# Tango_V1_0.net
KiCad netlist of a schematic drawn in Altium Designer
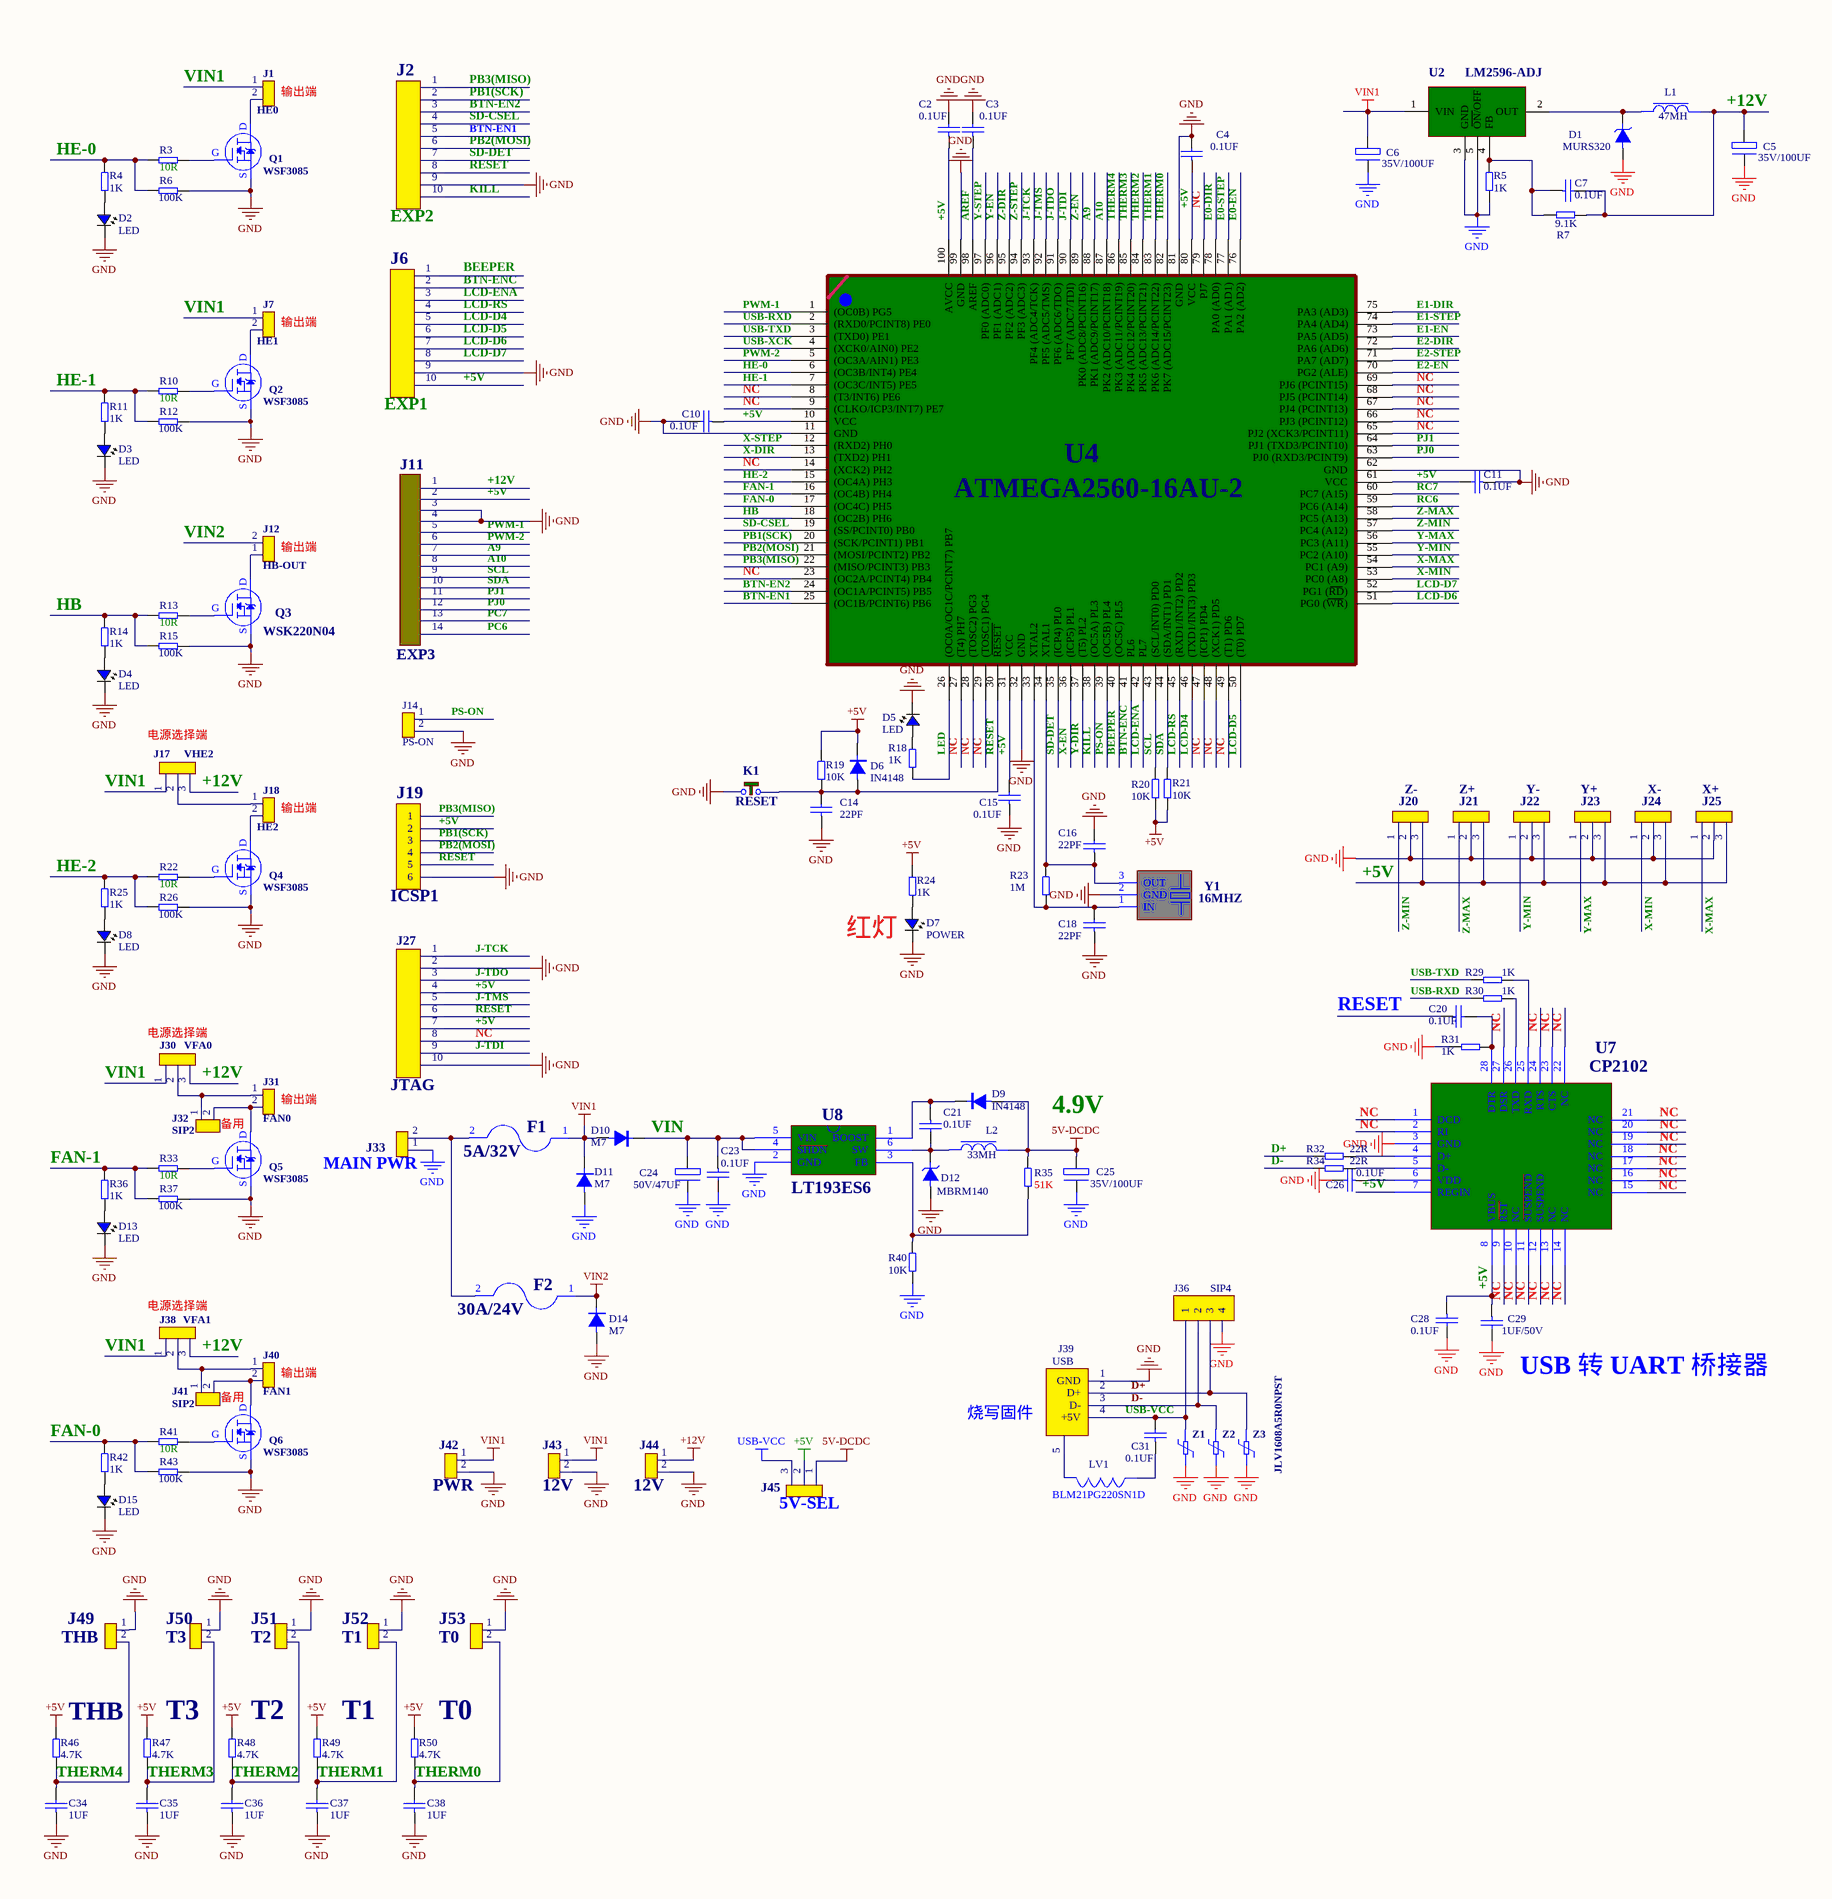
[diagram p0: Tango V1.0.SchDoc, left]
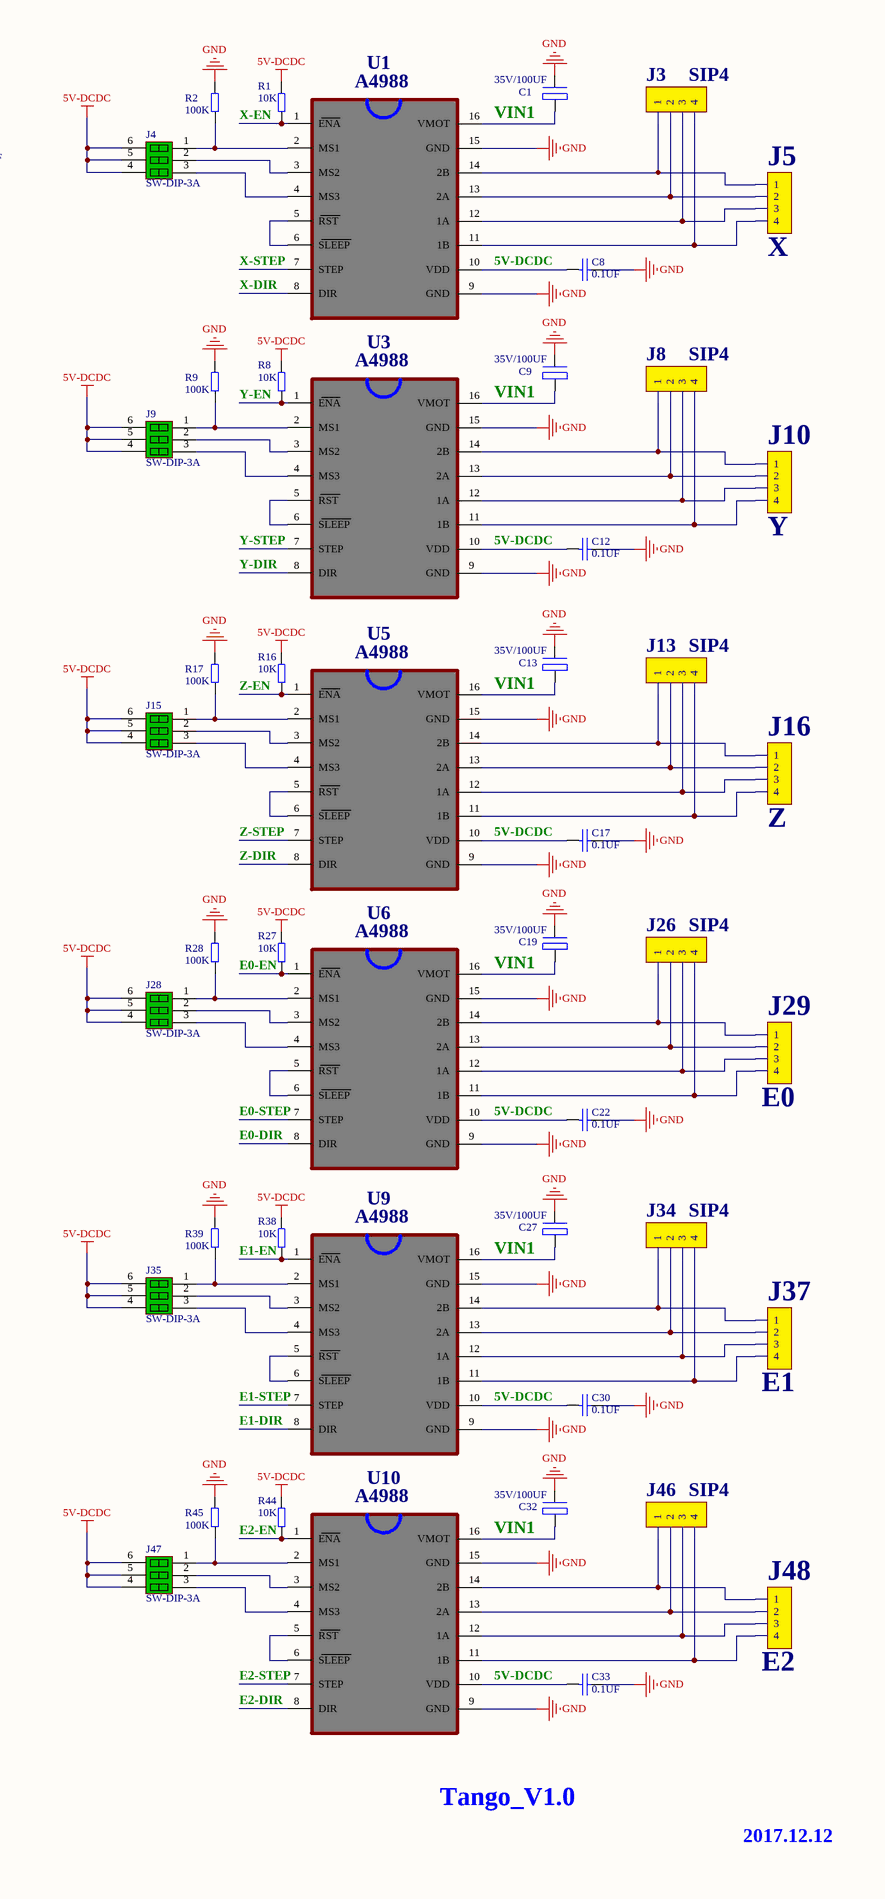
[diagram p1: Tango V1.0.SchDoc, right]

(export (version "E")
  (design (tool "Eeschema 10.0.6"))
  (components
    (comp (ref "C1") (value "35V/100UF") (footprint "35V/100UF-2") (libsource (lib "liroqi") (part "C")))
    (comp (ref "C2") (value "0.1UF") (footprint "0603N") (libsource (lib "liroqi") (part "CAP")))
    (comp (ref "C3") (value "0.1UF") (footprint "0603N") (libsource (lib "liroqi") (part "CAP")))
    (comp (ref "C4") (value "0.1UF") (footprint "0603N") (libsource (lib "liroqi") (part "CAP")))
    (comp (ref "C5") (value "35V/100UF") (footprint "35V/100UF-2") (libsource (lib "liroqi") (part "C")))
    (comp (ref "C6") (value "35V/100UF") (footprint "35V/100UF-2") (libsource (lib "liroqi") (part "C")))
    (comp (ref "C7") (value "0.1UF") (footprint "0603N") (libsource (lib "liroqi") (part "CAP")))
    (comp (ref "C8") (value "0.1UF") (footprint "0603N") (libsource (lib "liroqi") (part "CAP")))
    (comp (ref "C9") (value "35V/100UF") (footprint "35V/100UF-2") (libsource (lib "liroqi") (part "C")))
    (comp (ref "C10") (value "0.1UF") (footprint "0603N") (libsource (lib "liroqi") (part "CAP")))
    (comp (ref "C11") (value "0.1UF") (footprint "0603N") (libsource (lib "liroqi") (part "CAP")))
    (comp (ref "C12") (value "0.1UF") (footprint "0603N") (libsource (lib "liroqi") (part "CAP")))
    (comp (ref "C13") (value "35V/100UF") (footprint "35V/100UF-2") (libsource (lib "liroqi") (part "C")))
    (comp (ref "C14") (value "22PF") (footprint "0603N") (libsource (lib "liroqi") (part "CAP")))
    (comp (ref "C15") (value "0.1UF") (footprint "0603N") (libsource (lib "liroqi") (part "CAP")))
    (comp (ref "C16") (value "22PF") (footprint "0603N") (libsource (lib "liroqi") (part "CAP")))
    (comp (ref "C17") (value "0.1UF") (footprint "0603N") (libsource (lib "liroqi") (part "CAP")))
    (comp (ref "C18") (value "22PF") (footprint "0603N") (libsource (lib "liroqi") (part "CAP")))
    (comp (ref "C19") (value "35V/100UF") (footprint "35V/100UF-2") (libsource (lib "liroqi") (part "C")))
    (comp (ref "C20") (value "0.1UF") (footprint "0603N") (libsource (lib "liroqi") (part "CAP")))
    (comp (ref "C21") (value "0.1UF") (footprint "0603N") (libsource (lib "liroqi") (part "CAP")))
    (comp (ref "C22") (value "0.1UF") (footprint "0603N") (libsource (lib "liroqi") (part "CAP")))
    (comp (ref "C23") (value "0.1UF") (footprint "0603N") (libsource (lib "liroqi") (part "CAP")))
    (comp (ref "C24") (value "50V/47UF") (footprint "35V/100UF-2") (libsource (lib "liroqi") (part "C")))
    (comp (ref "C25") (value "35V/100UF") (footprint "35V/100UF-2") (libsource (lib "liroqi") (part "C")))
    (comp (ref "C26") (value "0.1UF") (footprint "0603N") (libsource (lib "liroqi") (part "CAP")))
    (comp (ref "C27") (value "35V/100UF") (footprint "35V/100UF-2") (libsource (lib "liroqi") (part "C")))
    (comp (ref "C28") (value "0.1UF") (footprint "0603N") (libsource (lib "liroqi") (part "CAP")))
    (comp (ref "C29") (value "1UF/50V") (footprint "0603N") (libsource (lib "liroqi") (part "CAP")))
    (comp (ref "C30") (value "0.1UF") (footprint "0603N") (libsource (lib "liroqi") (part "CAP")))
    (comp (ref "C31") (value "0.1UF") (footprint "0603N") (libsource (lib "liroqi") (part "CAP")))
    (comp (ref "C32") (value "35V/100UF") (footprint "35V/100UF-2") (libsource (lib "liroqi") (part "C")))
    (comp (ref "C33") (value "0.1UF") (footprint "0603N") (libsource (lib "liroqi") (part "CAP")))
    (comp (ref "C34") (value "1UF") (footprint "0805N") (libsource (lib "liroqi") (part "CAP")))
    (comp (ref "C35") (value "1UF") (footprint "0805N") (libsource (lib "liroqi") (part "CAP")))
    (comp (ref "C36") (value "1UF") (footprint "0805N") (libsource (lib "liroqi") (part "CAP")))
    (comp (ref "C37") (value "1UF") (footprint "0805N") (libsource (lib "liroqi") (part "CAP")))
    (comp (ref "C38") (value "1UF") (footprint "0805N") (libsource (lib "liroqi") (part "CAP")))
    (comp (ref "D1") (value "MURS320") (footprint "DO-214AB") (libsource (lib "liroqi") (part "ZENEVR")))
    (comp (ref "D2") (value "LED") (footprint "LED-0603") (libsource (lib "liroqi") (part "LED")))
    (comp (ref "D3") (value "LED") (footprint "LED-0603") (libsource (lib "liroqi") (part "LED")))
    (comp (ref "D4") (value "LED") (footprint "LED-0603") (libsource (lib "liroqi") (part "LED")))
    (comp (ref "D5") (value "LED") (footprint "LED-0603") (libsource (lib "liroqi") (part "LED")))
    (comp (ref "D6") (value "IN4148") (footprint "1206-DIDEO") (libsource (lib "liroqi") (part "DIODE")))
    (comp (ref "D7") (value "POWER") (footprint "LED-0603") (libsource (lib "liroqi") (part "LED")))
    (comp (ref "D8") (value "LED") (footprint "LED-0603") (libsource (lib "liroqi") (part "LED")))
    (comp (ref "D9") (value "IN4148") (footprint "1206-DIDEO") (libsource (lib "liroqi") (part "DIODE")))
    (comp (ref "D10") (value "M7") (footprint "DO-214AC") (libsource (lib "liroqi") (part "DIODE")))
    (comp (ref "D11") (value "M7") (footprint "DO-214AC") (libsource (lib "liroqi") (part "DIODE")))
    (comp (ref "D12") (value "MBRM140") (footprint "MBRM140") (libsource (lib "liroqi") (part "ZENEVR")))
    (comp (ref "D13") (value "LED") (footprint "LED-0603") (libsource (lib "liroqi") (part "LED")))
    (comp (ref "D14") (value "M7") (footprint "DO-214AC") (libsource (lib "liroqi") (part "DIODE")))
    (comp (ref "D15") (value "LED") (footprint "LED-0603") (libsource (lib "liroqi") (part "LED")))
    (comp (ref "F1") (value "5A/32V") (footprint "1206") (libsource (lib "liroqi") (part "FUSE")))
    (comp (ref "F2") (value "30A/24V") (footprint "1206") (libsource (lib "liroqi") (part "FUSE")))
    (comp (ref "J1") (value "HE0") (footprint "5.08-2-B") (libsource (lib "") (part "SIP2_1")))
    (comp (ref "J2") (value "EXP2") (footprint "IDC10-2.54") (libsource (lib "liroqi") (part "SIP10")))
    (comp (ref "J3") (value "SIP4") (footprint "SIP4") (libsource (lib "") (part "SIP4_1")))
    (comp (ref "J4")
      (value "SW-DIP-3A")
      (footprint "Header 3X2-B")
      (libsource (lib "liroqi") (part "SW-DIP-3A"))
    )
    (comp (ref "J5") (value "X") (footprint "2.54-4P-2") (libsource (lib "liroqi") (part "SIP4")))
    (comp (ref "J6") (value "EXP1") (footprint "IDC10-2.54") (libsource (lib "liroqi") (part "SIP10")))
    (comp (ref "J7") (value "HE1") (footprint "5.08-2-B") (libsource (lib "") (part "SIP2_1")))
    (comp (ref "J8") (value "SIP4") (footprint "SIP4") (libsource (lib "") (part "SIP4_1")))
    (comp (ref "J9")
      (value "SW-DIP-3A")
      (footprint "Header 3X2-B")
      (libsource (lib "liroqi") (part "SW-DIP-3A"))
    )
    (comp (ref "J10") (value "Y") (footprint "2.54-4P-2") (libsource (lib "liroqi") (part "SIP4")))
    (comp (ref "J11") (value "EXP3") (footprint "Header 7X2") (libsource (lib "liroqi") (part "SIP14")))
    (comp (ref "J12") (value "HB-OUT") (footprint "5.08-2") (libsource (lib "") (part "SIP2_3")))
    (comp (ref "J13") (value "SIP4") (footprint "SIP4") (libsource (lib "") (part "SIP4_1")))
    (comp (ref "J14") (value "PS-ON") (footprint "SIP2") (libsource (lib "") (part "SIP2_2")))
    (comp (ref "J15")
      (value "SW-DIP-3A")
      (footprint "Header 3X2-B")
      (libsource (lib "liroqi") (part "SW-DIP-3A"))
    )
    (comp (ref "J16") (value "Z") (footprint "2.54-4P-2") (libsource (lib "liroqi") (part "SIP4")))
    (comp (ref "J17") (value "VHE2") (footprint "SIP3") (libsource (lib "liroqi") (part "SIP3")))
    (comp (ref "J18") (value "HE2") (footprint "5.08-2-B") (libsource (lib "") (part "SIP2_1")))
    (comp (ref "J19") (value "ICSP1") (footprint "Header 3X2") (libsource (lib "liroqi") (part "SIP6")))
    (comp (ref "J20") (value "Z-") (footprint "2.54-3P-2") (libsource (lib "liroqi") (part "SIP3")))
    (comp (ref "J21") (value "Z+") (footprint "2.54-3P-2") (libsource (lib "liroqi") (part "SIP3")))
    (comp (ref "J22") (value "Y-") (footprint "2.54-3P-2") (libsource (lib "liroqi") (part "SIP3")))
    (comp (ref "J23") (value "Y+") (footprint "2.54-3P-2") (libsource (lib "liroqi") (part "SIP3")))
    (comp (ref "J24") (value "X-") (footprint "2.54-3P-2") (libsource (lib "liroqi") (part "SIP3")))
    (comp (ref "J25") (value "X+") (footprint "2.54-3P-2") (libsource (lib "liroqi") (part "SIP3")))
    (comp (ref "J26") (value "SIP4") (footprint "SIP4") (libsource (lib "") (part "SIP4_1")))
    (comp (ref "J27") (value "JTAG") (footprint "Header 5X2") (libsource (lib "liroqi") (part "SIP10")))
    (comp (ref "J28")
      (value "SW-DIP-3A")
      (footprint "Header 3X2-B")
      (libsource (lib "liroqi") (part "SW-DIP-3A"))
    )
    (comp (ref "J29") (value "E0") (footprint "2.54-4P-2") (libsource (lib "liroqi") (part "SIP4")))
    (comp (ref "J30") (value "VFA0") (footprint "SIP3") (libsource (lib "liroqi") (part "SIP3")))
    (comp (ref "J31") (value "FAN0") (footprint "5.08-2-B") (libsource (lib "") (part "SIP2_1")))
    (comp (ref "J32") (value "SIP2") (footprint "SIP2") (libsource (lib "liroqi") (part "SIP2")))
    (comp (ref "J33") (value "MAIN PWR") (footprint "5.08-2") (libsource (lib "liroqi") (part "SIP2")))
    (comp (ref "J34") (value "SIP4") (footprint "SIP4") (libsource (lib "") (part "SIP4_1")))
    (comp (ref "J35")
      (value "SW-DIP-3A")
      (footprint "Header 3X2-B")
      (libsource (lib "liroqi") (part "SW-DIP-3A"))
    )
    (comp (ref "J36") (value "SIP4") (footprint "SIP4") (libsource (lib "") (part "SIP4_1")))
    (comp (ref "J37") (value "E1") (footprint "2.54-4P-2") (libsource (lib "liroqi") (part "SIP4")))
    (comp (ref "J38") (value "VFA1") (footprint "SIP3") (libsource (lib "liroqi") (part "SIP3")))
    (comp (ref "J39") (value "USB") (footprint "USB-B-3") (libsource (lib "liroqi") (part "SIP5-USB")))
    (comp (ref "J40") (value "FAN1") (footprint "5.08-2-B") (libsource (lib "") (part "SIP2_1")))
    (comp (ref "J41") (value "SIP2") (footprint "SIP2") (libsource (lib "liroqi") (part "SIP2")))
    (comp (ref "J42") (value "PWR") (footprint "SIP2") (libsource (lib "") (part "SIP2_2")))
    (comp (ref "J43") (value "12V") (footprint "2.54-2P-2") (libsource (lib "") (part "SIP2_2")))
    (comp (ref "J44") (value "12V") (footprint "2.54-2P-2") (libsource (lib "") (part "SIP2_2")))
    (comp (ref "J45") (value "5V-SEL") (footprint "SIP3") (libsource (lib "") (part "SIP3_1")))
    (comp (ref "J46") (value "SIP4") (footprint "SIP4") (libsource (lib "") (part "SIP4_1")))
    (comp (ref "J47")
      (value "SW-DIP-3A")
      (footprint "Header 3X2-B")
      (libsource (lib "liroqi") (part "SW-DIP-3A"))
    )
    (comp (ref "J48") (value "E2") (footprint "2.54-4P-2") (libsource (lib "liroqi") (part "SIP4")))
    (comp (ref "J49") (value "THB") (footprint "2.54-2P-2") (libsource (lib "") (part "SIP2_2")))
    (comp (ref "J50") (value "T3") (footprint "2.54-2P-2") (libsource (lib "") (part "SIP2_2")))
    (comp (ref "J51") (value "T2") (footprint "2.54-2P-2") (libsource (lib "") (part "SIP2_2")))
    (comp (ref "J52") (value "T1") (footprint "2.54-2P-2") (libsource (lib "") (part "SIP2_2")))
    (comp (ref "J53") (value "T0") (footprint "2.54-2P-2") (libsource (lib "") (part "SIP2_2")))
    (comp (ref "K1") (value "RESET") (footprint "K-VX") (libsource (lib "liroqi") (part "K3")))
    (comp (ref "L1") (value "47MH") (footprint "15MH") (libsource (lib "liroqi") (part "L1")))
    (comp (ref "L2") (value "33MH") (footprint "7.5*7.5") (libsource (lib "liroqi") (part "L1")))
    (comp (ref "LV1") (value "BLM21PG220SN1D") (footprint "0805N") (libsource (lib "liroqi") (part "L")))
    (comp (ref "Q1") (value "WSF3085") (footprint "TO-252-B") (libsource (lib "liroqi") (part "VS3060AD")))
    (comp (ref "Q2") (value "WSF3085") (footprint "TO-252-B") (libsource (lib "liroqi") (part "VS3060AD")))
    (comp (ref "Q3") (value "WSK220N04") (footprint "TO-263-B") (libsource (lib "liroqi") (part "NMOS")))
    (comp (ref "Q4") (value "WSF3085") (footprint "TO-252-B") (libsource (lib "liroqi") (part "VS3060AD")))
    (comp (ref "Q5") (value "WSF3085") (footprint "TO-252-B") (libsource (lib "liroqi") (part "VS3060AD")))
    (comp (ref "Q6") (value "WSF3085") (footprint "TO-252-B") (libsource (lib "liroqi") (part "VS3060AD")))
    (comp (ref "R1") (value "10K") (footprint "0603N") (libsource (lib "liroqi") (part "RES")))
    (comp (ref "R2") (value "100K") (footprint "0603N") (libsource (lib "liroqi") (part "RES")))
    (comp (ref "R3") (value "10R") (footprint "0603N") (libsource (lib "liroqi") (part "RES")))
    (comp (ref "R4") (value "1K") (footprint "0603N") (libsource (lib "liroqi") (part "RES")))
    (comp (ref "R5") (value "1K") (footprint "0603N") (libsource (lib "liroqi") (part "RES")))
    (comp (ref "R6") (value "100K") (footprint "0603N") (libsource (lib "liroqi") (part "RES")))
    (comp (ref "R7") (value "9.1K") (footprint "0603N") (libsource (lib "liroqi") (part "RES")))
    (comp (ref "R8") (value "10K") (footprint "0603N") (libsource (lib "liroqi") (part "RES")))
    (comp (ref "R9") (value "100K") (footprint "0603N") (libsource (lib "liroqi") (part "RES")))
    (comp (ref "R10") (value "10R") (footprint "0603N") (libsource (lib "liroqi") (part "RES")))
    (comp (ref "R11") (value "1K") (footprint "0603N") (libsource (lib "liroqi") (part "RES")))
    (comp (ref "R12") (value "100K") (footprint "0603N") (libsource (lib "liroqi") (part "RES")))
    (comp (ref "R13") (value "10R") (footprint "0603N") (libsource (lib "liroqi") (part "RES")))
    (comp (ref "R14") (value "1K") (footprint "0603N") (libsource (lib "liroqi") (part "RES")))
    (comp (ref "R15") (value "100K") (footprint "0603N") (libsource (lib "liroqi") (part "RES")))
    (comp (ref "R16") (value "10K") (footprint "0603N") (libsource (lib "liroqi") (part "RES")))
    (comp (ref "R17") (value "100K") (footprint "0603N") (libsource (lib "liroqi") (part "RES")))
    (comp (ref "R18") (value "1K") (footprint "0603N") (libsource (lib "liroqi") (part "RES")))
    (comp (ref "R19") (value "10K") (footprint "0603N") (libsource (lib "liroqi") (part "RES")))
    (comp (ref "R20") (value "10K") (footprint "0603N") (libsource (lib "liroqi") (part "RES")))
    (comp (ref "R21") (value "10K") (footprint "0603N") (libsource (lib "liroqi") (part "RES")))
    (comp (ref "R22") (value "10R") (footprint "0603N") (libsource (lib "liroqi") (part "RES")))
    (comp (ref "R23") (value "1M") (footprint "0603N") (libsource (lib "liroqi") (part "RES")))
    (comp (ref "R24") (value "1K") (footprint "0603N") (libsource (lib "liroqi") (part "RES")))
    (comp (ref "R25") (value "1K") (footprint "0603N") (libsource (lib "liroqi") (part "RES")))
    (comp (ref "R26") (value "100K") (footprint "0603N") (libsource (lib "liroqi") (part "RES")))
    (comp (ref "R27") (value "10K") (footprint "0603N") (libsource (lib "liroqi") (part "RES")))
    (comp (ref "R28") (value "100K") (footprint "0603N") (libsource (lib "liroqi") (part "RES")))
    (comp (ref "R29") (value "1K") (footprint "0603N") (libsource (lib "liroqi") (part "RES")))
    (comp (ref "R30") (value "1K") (footprint "0603N") (libsource (lib "liroqi") (part "RES")))
    (comp (ref "R31") (value "1K") (footprint "0603N") (libsource (lib "liroqi") (part "RES")))
    (comp (ref "R32") (value "22R") (footprint "0603N") (libsource (lib "liroqi") (part "RES")))
    (comp (ref "R33") (value "10R") (footprint "0603N") (libsource (lib "liroqi") (part "RES")))
    (comp (ref "R34") (value "22R") (footprint "0603N") (libsource (lib "liroqi") (part "RES")))
    (comp (ref "R35") (value "51K") (footprint "0603N") (libsource (lib "liroqi") (part "RES")))
    (comp (ref "R36") (value "1K") (footprint "0603N") (libsource (lib "liroqi") (part "RES")))
    (comp (ref "R37") (value "100K") (footprint "0603N") (libsource (lib "liroqi") (part "RES")))
    (comp (ref "R38") (value "10K") (footprint "0603N") (libsource (lib "liroqi") (part "RES")))
    (comp (ref "R39") (value "100K") (footprint "0603N") (libsource (lib "liroqi") (part "RES")))
    (comp (ref "R40") (value "10K") (footprint "0603N") (libsource (lib "liroqi") (part "RES")))
    (comp (ref "R41") (value "10R") (footprint "0603N") (libsource (lib "liroqi") (part "RES")))
    (comp (ref "R42") (value "1K") (footprint "0603N") (libsource (lib "liroqi") (part "RES")))
    (comp (ref "R43") (value "100K") (footprint "0603N") (libsource (lib "liroqi") (part "RES")))
    (comp (ref "R44") (value "10K") (footprint "0603N") (libsource (lib "liroqi") (part "RES")))
    (comp (ref "R45") (value "100K") (footprint "0603N") (libsource (lib "liroqi") (part "RES")))
    (comp (ref "R46") (value "4.7K") (footprint "0603N") (libsource (lib "liroqi") (part "RES")))
    (comp (ref "R47") (value "4.7K") (footprint "0603N") (libsource (lib "liroqi") (part "RES")))
    (comp (ref "R48") (value "4.7K") (footprint "0603N") (libsource (lib "liroqi") (part "RES")))
    (comp (ref "R49") (value "4.7K") (footprint "0603N") (libsource (lib "liroqi") (part "RES")))
    (comp (ref "R50") (value "4.7K") (footprint "0603N") (libsource (lib "liroqi") (part "RES")))
    (comp (ref "U1") (value "A4988") (footprint "A4988") (libsource (lib "liroqi") (part "A4988")))
    (comp (ref "U2") (value "LM2596-ADJ") (footprint "TO-263(S)") (libsource (lib "liroqi") (part "LM2596")))
    (comp (ref "U3") (value "A4988") (footprint "A4988") (libsource (lib "liroqi") (part "A4988")))
    (comp (ref "U4")
      (value "ATMEGA2560-16AU-2")
      (footprint "TQFP-100-B")
      (libsource (lib "liroqi") (part "ATMEGA2560-16AU-2"))
    )
    (comp (ref "U5") (value "A4988") (footprint "A4988") (libsource (lib "liroqi") (part "A4988")))
    (comp (ref "U6") (value "A4988") (footprint "A4988") (libsource (lib "liroqi") (part "A4988")))
    (comp (ref "U7") (value "CP2102") (footprint "QFN-28") (libsource (lib "liroqi") (part "CP2102")))
    (comp (ref "U8") (value "LT193ES6") (footprint "SOT23-6") (libsource (lib "liroqi") (part "LT1933ES6")))
    (comp (ref "U9") (value "A4988") (footprint "A4988") (libsource (lib "liroqi") (part "A4988")))
    (comp (ref "U10") (value "A4988") (footprint "A4988") (libsource (lib "liroqi") (part "A4988")))
    (comp (ref "Y1") (value "16MHZ") (footprint "SMD-3") (libsource (lib "liroqi") (part "SMD-3")))
    (comp (ref "Z1") (value "JLV1608A5R0NPST") (footprint "0603N") (libsource (lib "liroqi") (part "RV?")))
    (comp (ref "Z2") (value "JLV1608A5R0NPST") (footprint "0603N") (libsource (lib "liroqi") (part "RV?")))
    (comp (ref "Z3") (value "JLV1608A5R0NPST") (footprint "0603N") (libsource (lib "liroqi") (part "RV?")))
  )
  (nets
    (net (code "1") (name "+5V") (class "Default")
      (node (ref "C10") (pin "1") (pinfunction "1_1") (pintype "passive"))
      (node (ref "C11") (pin "2") (pinfunction "2_2") (pintype "passive"))
      (node (ref "C15") (pin "2") (pinfunction "2_2") (pintype "passive"))
      (node (ref "C2") (pin "1") (pinfunction "1_1") (pintype "passive"))
      (node (ref "C28") (pin "1") (pinfunction "1_1") (pintype "passive"))
      (node (ref "C29") (pin "1") (pinfunction "1_1") (pintype "passive"))
      (node (ref "C4") (pin "1") (pinfunction "1_1") (pintype "passive"))
      (node (ref "D6") (pin "2") (pinfunction "K_2") (pintype "passive"))
      (node (ref "J11") (pin "2") (pinfunction "2_2") (pintype "passive"))
      (node (ref "J19") (pin "2") (pinfunction "2_2") (pintype "passive"))
      (node (ref "J20") (pin "3") (pinfunction "3_3") (pintype "passive"))
      (node (ref "J21") (pin "3") (pinfunction "3_3") (pintype "passive"))
      (node (ref "J22") (pin "3") (pinfunction "3_3") (pintype "passive"))
      (node (ref "J23") (pin "3") (pinfunction "3_3") (pintype "passive"))
      (node (ref "J24") (pin "3") (pinfunction "3_3") (pintype "passive"))
      (node (ref "J25") (pin "3") (pinfunction "3_3") (pintype "passive"))
      (node (ref "J27") (pin "4") (pinfunction "4_4") (pintype "passive"))
      (node (ref "J27") (pin "7") (pinfunction "7_7") (pintype "passive"))
      (node (ref "J45") (pin "2") (pinfunction "2_2") (pintype "passive"))
      (node (ref "J6") (pin "10") (pinfunction "10_10") (pintype "passive"))
      (node (ref "R19") (pin "1") (pinfunction "1_1") (pintype "passive"))
      (node (ref "R20") (pin "2") (pinfunction "2_2") (pintype "passive"))
      (node (ref "R21") (pin "2") (pinfunction "2_2") (pintype "passive"))
      (node (ref "R24") (pin "2") (pinfunction "2_2") (pintype "passive"))
      (node (ref "R46") (pin "1") (pinfunction "1_1") (pintype "passive"))
      (node (ref "R47") (pin "1") (pinfunction "1_1") (pintype "passive"))
      (node (ref "R48") (pin "1") (pinfunction "1_1") (pintype "passive"))
      (node (ref "R49") (pin "1") (pinfunction "1_1") (pintype "passive"))
      (node (ref "R50") (pin "1") (pinfunction "1_1") (pintype "passive"))
      (node (ref "U4") (pin "10") (pinfunction "VCC_10") (pintype "passive"))
      (node (ref "U4") (pin "100") (pinfunction "AVCC_100") (pintype "passive"))
      (node (ref "U4") (pin "31") (pinfunction "VCC_31") (pintype "passive"))
      (node (ref "U4") (pin "61") (pinfunction "VCC_61") (pintype "passive"))
      (node (ref "U4") (pin "80") (pinfunction "VCC_80") (pintype "passive"))
      (node (ref "U7") (pin "7") (pinfunction "REGIN_7") (pintype "passive"))
      (node (ref "U7") (pin "8") (pinfunction "VBUS_8") (pintype "passive"))
    )
    (net (code "2") (name "+12V") (class "Default")
      (node (ref "C5") (pin "1") (pinfunction "+_1") (pintype "passive"))
      (node (ref "C7") (pin "2") (pinfunction "2_2") (pintype "passive"))
      (node (ref "J11") (pin "1") (pinfunction "1_1") (pintype "passive"))
      (node (ref "J17") (pin "3") (pinfunction "3_3") (pintype "passive"))
      (node (ref "J30") (pin "3") (pinfunction "3_3") (pintype "passive"))
      (node (ref "J38") (pin "3") (pinfunction "3_3") (pintype "passive"))
      (node (ref "J44") (pin "1") (pinfunction "1_1") (pintype "passive"))
      (node (ref "L1") (pin "2") (pinfunction "2_2") (pintype "passive"))
      (node (ref "R7") (pin "2") (pinfunction "2_2") (pintype "passive"))
    )
    (net (code "3") (name "/A9") (class "Default")
      (node (ref "J11") (pin "7") (pinfunction "7_7") (pintype "passive"))
      (node (ref "U4") (pin "88") (pinfunction "PK1_(ADC9/PCINT17)_88") (pintype "passive"))
    )
    (net (code "4") (name "/A10") (class "Default")
      (node (ref "J11") (pin "8") (pinfunction "8_8") (pintype "passive"))
      (node (ref "U4") (pin "87") (pinfunction "PK2_(ADC10/PCINT18)_87") (pintype "passive"))
    )
    (net (code "5") (name "/AREF") (class "Default")
      (node (ref "C3") (pin "1") (pinfunction "1_1") (pintype "passive"))
      (node (ref "U4") (pin "98") (pinfunction "AREF_98") (pintype "passive"))
    )
    (net (code "6") (name "/BEEPER") (class "Default")
      (node (ref "J6") (pin "1") (pinfunction "1_1") (pintype "passive"))
      (node (ref "U4") (pin "40") (pinfunction "(OC5C)_PL5_40") (pintype "passive"))
    )
    (net (code "7") (name "/BTN-EN1") (class "Default")
      (node (ref "J2") (pin "5") (pinfunction "5_5") (pintype "passive"))
      (node (ref "U4") (pin "25") (pinfunction "(OC1B/PCINT6)_PB6_25") (pintype "passive"))
    )
    (net (code "8") (name "/BTN-EN2") (class "Default")
      (node (ref "J2") (pin "3") (pinfunction "3_3") (pintype "passive"))
      (node (ref "U4") (pin "24") (pinfunction "(OC1A/PCINT5)_PB5_24") (pintype "passive"))
    )
    (net (code "9") (name "/BTN-ENC") (class "Default")
      (node (ref "J6") (pin "2") (pinfunction "2_2") (pintype "passive"))
      (node (ref "U4") (pin "41") (pinfunction "PL6_41") (pintype "passive"))
    )
    (net (code "10") (name "/D+") (class "Default")
      (node (ref "J36") (pin "3") (pinfunction "3_3") (pintype "passive"))
      (node (ref "J39") (pin "2") (pinfunction "D+_2") (pintype "passive"))
      (node (ref "R32") (pin "2") (pinfunction "2_2") (pintype "passive"))
      (node (ref "Z3") (pin "2") (pinfunction "2_2") (pintype "passive"))
    )
    (net (code "11") (name "/D-") (class "Default")
      (node (ref "J36") (pin "2") (pinfunction "2_2") (pintype "passive"))
      (node (ref "J39") (pin "3") (pinfunction "D-_3") (pintype "passive"))
      (node (ref "R34") (pin "2") (pinfunction "2_2") (pintype "passive"))
      (node (ref "Z2") (pin "2") (pinfunction "2_2") (pintype "passive"))
    )
    (net (code "12") (name "/E0-DIR") (class "Default")
      (node (ref "U4") (pin "78") (pinfunction "PA0_(AD0)_78") (pintype "passive"))
      (node (ref "U6") (pin "8") (pinfunction "DIR_8") (pintype "passive"))
    )
    (net (code "13") (name "/E0-EN") (class "Default")
      (node (ref "R27") (pin "2") (pinfunction "2_2") (pintype "passive"))
      (node (ref "U4") (pin "76") (pinfunction "PA2_(AD2)_76") (pintype "passive"))
      (node (ref "U6") (pin "1") (pinfunction "ENA_1") (pintype "passive"))
    )
    (net (code "14") (name "/E0-STEP") (class "Default")
      (node (ref "U4") (pin "77") (pinfunction "PA1_(AD1)_77") (pintype "passive"))
      (node (ref "U6") (pin "7") (pinfunction "STEP_7") (pintype "passive"))
    )
    (net (code "15") (name "/E1-DIR") (class "Default")
      (node (ref "U4") (pin "75") (pinfunction "PA3_(AD3)_75") (pintype "passive"))
      (node (ref "U9") (pin "8") (pinfunction "DIR_8") (pintype "passive"))
    )
    (net (code "16") (name "/E1-EN") (class "Default")
      (node (ref "R38") (pin "2") (pinfunction "2_2") (pintype "passive"))
      (node (ref "U4") (pin "73") (pinfunction "PA5_(AD5)_73") (pintype "passive"))
      (node (ref "U9") (pin "1") (pinfunction "ENA_1") (pintype "passive"))
    )
    (net (code "17") (name "/E1-STEP") (class "Default")
      (node (ref "U4") (pin "74") (pinfunction "PA4_(AD4)_74") (pintype "passive"))
      (node (ref "U9") (pin "7") (pinfunction "STEP_7") (pintype "passive"))
    )
    (net (code "18") (name "/E2-DIR") (class "Default")
      (node (ref "U10") (pin "8") (pinfunction "DIR_8") (pintype "passive"))
      (node (ref "U4") (pin "72") (pinfunction "PA6_(AD6)_72") (pintype "passive"))
    )
    (net (code "19") (name "/E2-EN") (class "Default")
      (node (ref "R44") (pin "2") (pinfunction "2_2") (pintype "passive"))
      (node (ref "U10") (pin "1") (pinfunction "ENA_1") (pintype "passive"))
      (node (ref "U4") (pin "70") (pinfunction "PG2_(ALE)_70") (pintype "passive"))
    )
    (net (code "20") (name "/E2-STEP") (class "Default")
      (node (ref "U10") (pin "7") (pinfunction "STEP_7") (pintype "passive"))
      (node (ref "U4") (pin "71") (pinfunction "PA7_(AD7)_71") (pintype "passive"))
    )
    (net (code "21") (name "/FAN-0") (class "Default")
      (node (ref "R41") (pin "2") (pinfunction "2_2") (pintype "passive"))
      (node (ref "R42") (pin "1") (pinfunction "1_1") (pintype "passive"))
      (node (ref "R43") (pin "2") (pinfunction "2_2") (pintype "passive"))
      (node (ref "U4") (pin "17") (pinfunction "(OC4C)_PH5_17") (pintype "passive"))
    )
    (net (code "22") (name "/FAN-1") (class "Default")
      (node (ref "R33") (pin "2") (pinfunction "2_2") (pintype "passive"))
      (node (ref "R36") (pin "1") (pinfunction "1_1") (pintype "passive"))
      (node (ref "R37") (pin "2") (pinfunction "2_2") (pintype "passive"))
      (node (ref "U4") (pin "16") (pinfunction "(OC4B)_PH4_16") (pintype "passive"))
    )
    (net (code "23") (name "/HB") (class "Default")
      (node (ref "R13") (pin "2") (pinfunction "2_2") (pintype "passive"))
      (node (ref "R14") (pin "1") (pinfunction "1_1") (pintype "passive"))
      (node (ref "R15") (pin "2") (pinfunction "2_2") (pintype "passive"))
      (node (ref "U4") (pin "18") (pinfunction "(OC2B)_PH6_18") (pintype "passive"))
    )
    (net (code "24") (name "/HE-0") (class "Default")
      (node (ref "R3") (pin "2") (pinfunction "2_2") (pintype "passive"))
      (node (ref "R4") (pin "1") (pinfunction "1_1") (pintype "passive"))
      (node (ref "R6") (pin "2") (pinfunction "2_2") (pintype "passive"))
      (node (ref "U4") (pin "6") (pinfunction "(OC3B/INT4)_PE4_6") (pintype "passive"))
    )
    (net (code "25") (name "/HE-1") (class "Default")
      (node (ref "R10") (pin "2") (pinfunction "2_2") (pintype "passive"))
      (node (ref "R11") (pin "1") (pinfunction "1_1") (pintype "passive"))
      (node (ref "R12") (pin "2") (pinfunction "2_2") (pintype "passive"))
      (node (ref "U4") (pin "7") (pinfunction "(OC3C/INT5)_PE5_7") (pintype "passive"))
    )
    (net (code "26") (name "/HE-2") (class "Default")
      (node (ref "R22") (pin "2") (pinfunction "2_2") (pintype "passive"))
      (node (ref "R25") (pin "1") (pinfunction "1_1") (pintype "passive"))
      (node (ref "R26") (pin "2") (pinfunction "2_2") (pintype "passive"))
      (node (ref "U4") (pin "15") (pinfunction "(OC4A)_PH3_15") (pintype "passive"))
    )
    (net (code "27") (name "/J-TCK") (class "Default")
      (node (ref "J27") (pin "1") (pinfunction "1_1") (pintype "passive"))
      (node (ref "U4") (pin "93") (pinfunction "PF4_(ADC4/TCK)_93") (pintype "passive"))
    )
    (net (code "28") (name "/J-TDI") (class "Default")
      (node (ref "J27") (pin "9") (pinfunction "9_9") (pintype "passive"))
      (node (ref "U4") (pin "90") (pinfunction "PF7_(ADC7/TDI)_90") (pintype "passive"))
    )
    (net (code "29") (name "/J-TDO") (class "Default")
      (node (ref "J27") (pin "3") (pinfunction "3_3") (pintype "passive"))
      (node (ref "U4") (pin "91") (pinfunction "PF6_(ADC6/TDO)_91") (pintype "passive"))
    )
    (net (code "30") (name "/J-TMS") (class "Default")
      (node (ref "J27") (pin "5") (pinfunction "5_5") (pintype "passive"))
      (node (ref "U4") (pin "92") (pinfunction "PF5_(ADC5/TMS)_92") (pintype "passive"))
    )
    (net (code "31") (name "/KILL") (class "Default")
      (node (ref "J2") (pin "10") (pinfunction "10_10") (pintype "passive"))
      (node (ref "U4") (pin "38") (pinfunction "(OC5A)_PL3_38") (pintype "passive"))
    )
    (net (code "32") (name "/LCD-D4") (class "Default")
      (node (ref "J6") (pin "5") (pinfunction "5_5") (pintype "passive"))
      (node (ref "U4") (pin "46") (pinfunction "(TXD1/INT3)_PD3_46") (pintype "passive"))
    )
    (net (code "33") (name "/LCD-D5") (class "Default")
      (node (ref "J6") (pin "6") (pinfunction "6_6") (pintype "passive"))
      (node (ref "U4") (pin "50") (pinfunction "(T0)_PD7_50") (pintype "passive"))
    )
    (net (code "34") (name "/LCD-D6") (class "Default")
      (node (ref "J6") (pin "7") (pinfunction "7_7") (pintype "passive"))
      (node (ref "U4") (pin "51") (pinfunction "PG0_(WR)_51") (pintype "passive"))
    )
    (net (code "35") (name "/LCD-D7") (class "Default")
      (node (ref "J6") (pin "8") (pinfunction "8_8") (pintype "passive"))
      (node (ref "U4") (pin "52") (pinfunction "PG1_(RD)_52") (pintype "passive"))
    )
    (net (code "36") (name "/LCD-ENA") (class "Default")
      (node (ref "J6") (pin "3") (pinfunction "3_3") (pintype "passive"))
      (node (ref "U4") (pin "42") (pinfunction "PL7_42") (pintype "passive"))
    )
    (net (code "37") (name "/LCD-RS") (class "Default")
      (node (ref "J6") (pin "4") (pinfunction "4_4") (pintype "passive"))
      (node (ref "U4") (pin "45") (pinfunction "(RXD1/INT2)_PD2_45") (pintype "passive"))
    )
    (net (code "38") (name "/LED") (class "Default")
      (node (ref "R18") (pin "2") (pinfunction "2_2") (pintype "passive"))
      (node (ref "U4") (pin "26") (pinfunction "(OC0A/OC1C/PCINT7)_PB7_26") (pintype "passive"))
    )
    (net (code "39") (name "/PB1(SCK)") (class "Default")
      (node (ref "J19") (pin "3") (pinfunction "3_3") (pintype "passive"))
      (node (ref "J2") (pin "2") (pinfunction "2_2") (pintype "passive"))
      (node (ref "U4") (pin "20") (pinfunction "(SCK/PCINT1)_PB1_20") (pintype "passive"))
    )
    (net (code "40") (name "/PB2(MOSI)") (class "Default")
      (node (ref "J19") (pin "4") (pinfunction "4_4") (pintype "passive"))
      (node (ref "J2") (pin "6") (pinfunction "6_6") (pintype "passive"))
      (node (ref "U4") (pin "21") (pinfunction "(MOSI/PCINT2)_PB2_21") (pintype "passive"))
    )
    (net (code "41") (name "/PB3(MISO)") (class "Default")
      (node (ref "J19") (pin "1") (pinfunction "1_1") (pintype "passive"))
      (node (ref "J2") (pin "1") (pinfunction "1_1") (pintype "passive"))
      (node (ref "U4") (pin "22") (pinfunction "(MISO/PCINT3)_PB3_22") (pintype "passive"))
    )
    (net (code "42") (name "/PC6") (class "Default")
      (node (ref "J11") (pin "14") (pinfunction "14_14") (pintype "passive"))
    )
    (net (code "43") (name "/PC7") (class "Default")
      (node (ref "J11") (pin "13") (pinfunction "13_13") (pintype "passive"))
    )
    (net (code "44") (name "/PJ0") (class "Default")
      (node (ref "J11") (pin "12") (pinfunction "12_12") (pintype "passive"))
      (node (ref "U4") (pin "63") (pinfunction "PJ0_(RXD3/PCINT9)_63") (pintype "passive"))
    )
    (net (code "45") (name "/PJ1") (class "Default")
      (node (ref "J11") (pin "11") (pinfunction "11_11") (pintype "passive"))
      (node (ref "U4") (pin "64") (pinfunction "PJ1_(TXD3/PCINT10)_64") (pintype "passive"))
    )
    (net (code "46") (name "/PS-ON") (class "Default")
      (node (ref "J14") (pin "1") (pinfunction "1_1") (pintype "passive"))
      (node (ref "U4") (pin "39") (pinfunction "(OC5B)_PL4_39") (pintype "passive"))
    )
    (net (code "47") (name "/PWM-1") (class "Default")
      (node (ref "J11") (pin "5") (pinfunction "5_5") (pintype "passive"))
      (node (ref "U4") (pin "1") (pinfunction "(OC0B)_PG5_1") (pintype "passive"))
    )
    (net (code "48") (name "/PWM-2") (class "Default")
      (node (ref "J11") (pin "6") (pinfunction "6_6") (pintype "passive"))
      (node (ref "U4") (pin "5") (pinfunction "(OC3A/AIN1)_PE3_5") (pintype "passive"))
    )
    (net (code "49") (name "/RC6") (class "Default")
      (node (ref "U4") (pin "59") (pinfunction "PC6_(A14)_59") (pintype "passive"))
    )
    (net (code "50") (name "/RC7") (class "Default")
      (node (ref "U4") (pin "60") (pinfunction "PC7_(A15)_60") (pintype "passive"))
    )
    (net (code "51") (name "/RESET") (class "Default")
      (node (ref "C14") (pin "2") (pinfunction "2_2") (pintype "passive"))
      (node (ref "C20") (pin "1") (pinfunction "1_1") (pintype "passive"))
      (node (ref "D6") (pin "1") (pinfunction "A_1") (pintype "passive"))
      (node (ref "J19") (pin "5") (pinfunction "5_5") (pintype "passive"))
      (node (ref "J2") (pin "8") (pinfunction "8_8") (pintype "passive"))
      (node (ref "J27") (pin "6") (pinfunction "6_6") (pintype "passive"))
      (node (ref "K1") (pin "2") (pinfunction "2_2") (pintype "passive"))
      (node (ref "R19") (pin "2") (pinfunction "2_2") (pintype "passive"))
      (node (ref "U4") (pin "30") (pinfunction "RESET_30") (pintype "passive"))
    )
    (net (code "52") (name "/SCL") (class "Default")
      (node (ref "J11") (pin "9") (pinfunction "9_9") (pintype "passive"))
      (node (ref "R20") (pin "1") (pinfunction "1_1") (pintype "passive"))
      (node (ref "U4") (pin "43") (pinfunction "(SCL/INT0)_PD0_43") (pintype "passive"))
    )
    (net (code "53") (name "/SD-CSEL") (class "Default")
      (node (ref "J2") (pin "4") (pinfunction "4_4") (pintype "passive"))
      (node (ref "U4") (pin "19") (pinfunction "(SS/PCINT0)_PB0_19") (pintype "passive"))
    )
    (net (code "54") (name "/SD-DET") (class "Default")
      (node (ref "J2") (pin "7") (pinfunction "7_7") (pintype "passive"))
      (node (ref "U4") (pin "35") (pinfunction "(ICP4)_PL0_35") (pintype "passive"))
    )
    (net (code "55") (name "/SDA") (class "Default")
      (node (ref "J11") (pin "10") (pinfunction "10_10") (pintype "passive"))
      (node (ref "R21") (pin "1") (pinfunction "1_1") (pintype "passive"))
      (node (ref "U4") (pin "44") (pinfunction "(SDA/INT1)_PD1_44") (pintype "passive"))
    )
    (net (code "56") (name "/THERM0") (class "Default")
      (node (ref "C38") (pin "2") (pinfunction "2_2") (pintype "passive"))
      (node (ref "J53") (pin "2") (pinfunction "2_2") (pintype "passive"))
      (node (ref "R50") (pin "2") (pinfunction "2_2") (pintype "passive"))
      (node (ref "U4") (pin "82") (pinfunction "PK7_(ADC15/PCINT23)_82") (pintype "passive"))
    )
    (net (code "57") (name "/THERM1") (class "Default")
      (node (ref "C37") (pin "2") (pinfunction "2_2") (pintype "passive"))
      (node (ref "J52") (pin "2") (pinfunction "2_2") (pintype "passive"))
      (node (ref "R49") (pin "2") (pinfunction "2_2") (pintype "passive"))
      (node (ref "U4") (pin "83") (pinfunction "PK6_(ADC14/PCINT22)_83") (pintype "passive"))
    )
    (net (code "58") (name "/THERM2") (class "Default")
      (node (ref "C36") (pin "2") (pinfunction "2_2") (pintype "passive"))
      (node (ref "J51") (pin "2") (pinfunction "2_2") (pintype "passive"))
      (node (ref "R48") (pin "2") (pinfunction "2_2") (pintype "passive"))
      (node (ref "U4") (pin "84") (pinfunction "PK5_(ADC13/PCINT21)_84") (pintype "passive"))
    )
    (net (code "59") (name "/THERM3") (class "Default")
      (node (ref "C35") (pin "2") (pinfunction "2_2") (pintype "passive"))
      (node (ref "J50") (pin "2") (pinfunction "2_2") (pintype "passive"))
      (node (ref "R47") (pin "2") (pinfunction "2_2") (pintype "passive"))
      (node (ref "U4") (pin "85") (pinfunction "PK4_(ADC12/PCINT20)_85") (pintype "passive"))
    )
    (net (code "60") (name "/THERM4") (class "Default")
      (node (ref "C34") (pin "2") (pinfunction "2_2") (pintype "passive"))
      (node (ref "J49") (pin "2") (pinfunction "2_2") (pintype "passive"))
      (node (ref "R46") (pin "2") (pinfunction "2_2") (pintype "passive"))
      (node (ref "U4") (pin "86") (pinfunction "PK3_(ADC11/PCINT19)_86") (pintype "passive"))
    )
    (net (code "61") (name "/USB-RXD") (class "Default")
      (node (ref "R30") (pin "1") (pinfunction "1_1") (pintype "passive"))
      (node (ref "U4") (pin "2") (pinfunction "(RXD0/PCINT8)_PE0_2") (pintype "passive"))
    )
    (net (code "62") (name "/USB-TXD") (class "Default")
      (node (ref "R29") (pin "1") (pinfunction "1_1") (pintype "passive"))
      (node (ref "U4") (pin "3") (pinfunction "(TXD0)_PE1_3") (pintype "passive"))
    )
    (net (code "63") (name "/USB-XCK") (class "Default")
      (node (ref "U4") (pin "4") (pinfunction "(XCK0/AIN0)_PE2_4") (pintype "passive"))
    )
    (net (code "64") (name "/VIN") (class "Default")
      (node (ref "C23") (pin "1") (pinfunction "1_1") (pintype "passive"))
      (node (ref "C24") (pin "1") (pinfunction "+_1") (pintype "passive"))
      (node (ref "D10") (pin "2") (pinfunction "K_2") (pintype "passive"))
      (node (ref "U8") (pin "4") (pinfunction "SHDN_4") (pintype "passive"))
      (node (ref "U8") (pin "5") (pinfunction "VIN_5") (pintype "passive"))
    )
    (net (code "65") (name "/X-DIR") (class "Default")
      (node (ref "U1") (pin "8") (pinfunction "DIR_8") (pintype "passive"))
      (node (ref "U4") (pin "13") (pinfunction "(TXD2)_PH1_13") (pintype "passive"))
    )
    (net (code "66") (name "/X-EN") (class "Default")
      (node (ref "R1") (pin "2") (pinfunction "2_2") (pintype "passive"))
      (node (ref "U1") (pin "1") (pinfunction "ENA_1") (pintype "passive"))
      (node (ref "U4") (pin "36") (pinfunction "(ICP5)_PL1_36") (pintype "passive"))
    )
    (net (code "67") (name "/X-MAX") (class "Default")
      (node (ref "J25") (pin "1") (pinfunction "1_1") (pintype "passive"))
      (node (ref "U4") (pin "54") (pinfunction "PC1_(A9)_54") (pintype "passive"))
    )
    (net (code "68") (name "/X-MIN") (class "Default")
      (node (ref "J24") (pin "1") (pinfunction "1_1") (pintype "passive"))
      (node (ref "U4") (pin "53") (pinfunction "PC0_(A8)_53") (pintype "passive"))
    )
    (net (code "69") (name "/X-STEP") (class "Default")
      (node (ref "U1") (pin "7") (pinfunction "STEP_7") (pintype "passive"))
      (node (ref "U4") (pin "12") (pinfunction "(RXD2)_PH0_12") (pintype "passive"))
    )
    (net (code "70") (name "/Y-DIR") (class "Default")
      (node (ref "U3") (pin "8") (pinfunction "DIR_8") (pintype "passive"))
      (node (ref "U4") (pin "37") (pinfunction "(T5)_PL2_37") (pintype "passive"))
    )
    (net (code "71") (name "/Y-EN") (class "Default")
      (node (ref "R8") (pin "2") (pinfunction "2_2") (pintype "passive"))
      (node (ref "U3") (pin "1") (pinfunction "ENA_1") (pintype "passive"))
      (node (ref "U4") (pin "96") (pinfunction "PF1_(ADC1)_96") (pintype "passive"))
    )
    (net (code "72") (name "/Y-MAX") (class "Default")
      (node (ref "J23") (pin "1") (pinfunction "1_1") (pintype "passive"))
      (node (ref "U4") (pin "56") (pinfunction "PC3_(A11)_56") (pintype "passive"))
    )
    (net (code "73") (name "/Y-MIN") (class "Default")
      (node (ref "J22") (pin "1") (pinfunction "1_1") (pintype "passive"))
      (node (ref "U4") (pin "55") (pinfunction "PC2_(A10)_55") (pintype "passive"))
    )
    (net (code "74") (name "/Y-STEP") (class "Default")
      (node (ref "U3") (pin "7") (pinfunction "STEP_7") (pintype "passive"))
      (node (ref "U4") (pin "97") (pinfunction "PF0_(ADC0)_97") (pintype "passive"))
    )
    (net (code "75") (name "/Z-DIR") (class "Default")
      (node (ref "U4") (pin "95") (pinfunction "PF2_(ADC2)_95") (pintype "passive"))
      (node (ref "U5") (pin "8") (pinfunction "DIR_8") (pintype "passive"))
    )
    (net (code "76") (name "/Z-EN") (class "Default")
      (node (ref "R16") (pin "2") (pinfunction "2_2") (pintype "passive"))
      (node (ref "U4") (pin "89") (pinfunction "PK0_(ADC8/PCINT16)_89") (pintype "passive"))
      (node (ref "U5") (pin "1") (pinfunction "ENA_1") (pintype "passive"))
    )
    (net (code "77") (name "/Z-MAX") (class "Default")
      (node (ref "J21") (pin "1") (pinfunction "1_1") (pintype "passive"))
      (node (ref "U4") (pin "58") (pinfunction "PC5_(A13)_58") (pintype "passive"))
    )
    (net (code "78") (name "/Z-MIN") (class "Default")
      (node (ref "J20") (pin "1") (pinfunction "1_1") (pintype "passive"))
      (node (ref "U4") (pin "57") (pinfunction "PC4_(A12)_57") (pintype "passive"))
    )
    (net (code "79") (name "/Z-STEP") (class "Default")
      (node (ref "U4") (pin "94") (pinfunction "PF3_(ADC3)_94") (pintype "passive"))
      (node (ref "U5") (pin "7") (pinfunction "STEP_7") (pintype "passive"))
    )
    (net (code "80") (name "5V-DCDC") (class "Default")
      (node (ref "C12") (pin "1") (pinfunction "1_1") (pintype "passive"))
      (node (ref "C17") (pin "1") (pinfunction "1_1") (pintype "passive"))
      (node (ref "C22") (pin "1") (pinfunction "1_1") (pintype "passive"))
      (node (ref "C25") (pin "1") (pinfunction "+_1") (pintype "passive"))
      (node (ref "C30") (pin "1") (pinfunction "1_1") (pintype "passive"))
      (node (ref "C33") (pin "1") (pinfunction "1_1") (pintype "passive"))
      (node (ref "C8") (pin "1") (pinfunction "1_1") (pintype "passive"))
      (node (ref "D9") (pin "1") (pinfunction "A_1") (pintype "passive"))
      (node (ref "J15") (pin "4") (pinfunction "4_4") (pintype "passive"))
      (node (ref "J15") (pin "5") (pinfunction "5_5") (pintype "passive"))
      (node (ref "J15") (pin "6") (pinfunction "6_6") (pintype "passive"))
      (node (ref "J28") (pin "4") (pinfunction "4_4") (pintype "passive"))
      (node (ref "J28") (pin "5") (pinfunction "5_5") (pintype "passive"))
      (node (ref "J28") (pin "6") (pinfunction "6_6") (pintype "passive"))
      (node (ref "J35") (pin "4") (pinfunction "4_4") (pintype "passive"))
      (node (ref "J35") (pin "5") (pinfunction "5_5") (pintype "passive"))
      (node (ref "J35") (pin "6") (pinfunction "6_6") (pintype "passive"))
      (node (ref "J4") (pin "4") (pinfunction "4_4") (pintype "passive"))
      (node (ref "J4") (pin "5") (pinfunction "5_5") (pintype "passive"))
      (node (ref "J4") (pin "6") (pinfunction "6_6") (pintype "passive"))
      (node (ref "J45") (pin "1") (pinfunction "1_1") (pintype "passive"))
      (node (ref "J47") (pin "4") (pinfunction "4_4") (pintype "passive"))
      (node (ref "J47") (pin "5") (pinfunction "5_5") (pintype "passive"))
      (node (ref "J47") (pin "6") (pinfunction "6_6") (pintype "passive"))
      (node (ref "J9") (pin "4") (pinfunction "4_4") (pintype "passive"))
      (node (ref "J9") (pin "5") (pinfunction "5_5") (pintype "passive"))
      (node (ref "J9") (pin "6") (pinfunction "6_6") (pintype "passive"))
      (node (ref "L2") (pin "2") (pinfunction "2_2") (pintype "passive"))
      (node (ref "R1") (pin "1") (pinfunction "1_1") (pintype "passive"))
      (node (ref "R16") (pin "1") (pinfunction "1_1") (pintype "passive"))
      (node (ref "R27") (pin "1") (pinfunction "1_1") (pintype "passive"))
      (node (ref "R35") (pin "1") (pinfunction "1_1") (pintype "passive"))
      (node (ref "R38") (pin "1") (pinfunction "1_1") (pintype "passive"))
      (node (ref "R44") (pin "1") (pinfunction "1_1") (pintype "passive"))
      (node (ref "R8") (pin "1") (pinfunction "1_1") (pintype "passive"))
      (node (ref "U1") (pin "10") (pinfunction "VDD_10") (pintype "passive"))
      (node (ref "U10") (pin "10") (pinfunction "VDD_10") (pintype "passive"))
      (node (ref "U3") (pin "10") (pinfunction "VDD_10") (pintype "passive"))
      (node (ref "U5") (pin "10") (pinfunction "VDD_10") (pintype "passive"))
      (node (ref "U6") (pin "10") (pinfunction "VDD_10") (pintype "passive"))
      (node (ref "U9") (pin "10") (pinfunction "VDD_10") (pintype "passive"))
    )
    (net (code "81") (name "GND") (class "Default")
      (node (ref "C1") (pin "2") (pinfunction "-_2") (pintype "passive"))
      (node (ref "C10") (pin "2") (pinfunction "2_2") (pintype "passive"))
      (node (ref "C11") (pin "1") (pinfunction "1_1") (pintype "passive"))
      (node (ref "C12") (pin "2") (pinfunction "2_2") (pintype "passive"))
      (node (ref "C13") (pin "2") (pinfunction "-_2") (pintype "passive"))
      (node (ref "C14") (pin "1") (pinfunction "1_1") (pintype "passive"))
      (node (ref "C15") (pin "1") (pinfunction "1_1") (pintype "passive"))
      (node (ref "C16") (pin "2") (pinfunction "2_2") (pintype "passive"))
      (node (ref "C17") (pin "2") (pinfunction "2_2") (pintype "passive"))
      (node (ref "C18") (pin "1") (pinfunction "1_1") (pintype "passive"))
      (node (ref "C19") (pin "2") (pinfunction "-_2") (pintype "passive"))
      (node (ref "C2") (pin "2") (pinfunction "2_2") (pintype "passive"))
      (node (ref "C22") (pin "2") (pinfunction "2_2") (pintype "passive"))
      (node (ref "C23") (pin "2") (pinfunction "2_2") (pintype "passive"))
      (node (ref "C24") (pin "2") (pinfunction "-_2") (pintype "passive"))
      (node (ref "C25") (pin "2") (pinfunction "-_2") (pintype "passive"))
      (node (ref "C26") (pin "2") (pinfunction "2_2") (pintype "passive"))
      (node (ref "C27") (pin "2") (pinfunction "-_2") (pintype "passive"))
      (node (ref "C28") (pin "2") (pinfunction "2_2") (pintype "passive"))
      (node (ref "C29") (pin "2") (pinfunction "2_2") (pintype "passive"))
      (node (ref "C3") (pin "2") (pinfunction "2_2") (pintype "passive"))
      (node (ref "C30") (pin "2") (pinfunction "2_2") (pintype "passive"))
      (node (ref "C32") (pin "2") (pinfunction "-_2") (pintype "passive"))
      (node (ref "C33") (pin "2") (pinfunction "2_2") (pintype "passive"))
      (node (ref "C34") (pin "1") (pinfunction "1_1") (pintype "passive"))
      (node (ref "C35") (pin "1") (pinfunction "1_1") (pintype "passive"))
      (node (ref "C36") (pin "1") (pinfunction "1_1") (pintype "passive"))
      (node (ref "C37") (pin "1") (pinfunction "1_1") (pintype "passive"))
      (node (ref "C38") (pin "1") (pinfunction "1_1") (pintype "passive"))
      (node (ref "C4") (pin "2") (pinfunction "2_2") (pintype "passive"))
      (node (ref "C5") (pin "2") (pinfunction "-_2") (pintype "passive"))
      (node (ref "C6") (pin "2") (pinfunction "-_2") (pintype "passive"))
      (node (ref "C8") (pin "2") (pinfunction "2_2") (pintype "passive"))
      (node (ref "C9") (pin "2") (pinfunction "-_2") (pintype "passive"))
      (node (ref "D1") (pin "1") (pinfunction "A_1") (pintype "passive"))
      (node (ref "D11") (pin "1") (pinfunction "A_1") (pintype "passive"))
      (node (ref "D12") (pin "1") (pinfunction "A_1") (pintype "passive"))
      (node (ref "D13") (pin "2") (pinfunction "K_2") (pintype "passive"))
      (node (ref "D14") (pin "1") (pinfunction "A_1") (pintype "passive"))
      (node (ref "D15") (pin "2") (pinfunction "K_2") (pintype "passive"))
      (node (ref "D2") (pin "2") (pinfunction "K_2") (pintype "passive"))
      (node (ref "D3") (pin "2") (pinfunction "K_2") (pintype "passive"))
      (node (ref "D4") (pin "2") (pinfunction "K_2") (pintype "passive"))
      (node (ref "D5") (pin "2") (pinfunction "K_2") (pintype "passive"))
      (node (ref "D7") (pin "2") (pinfunction "K_2") (pintype "passive"))
      (node (ref "D8") (pin "2") (pinfunction "K_2") (pintype "passive"))
      (node (ref "J11") (pin "3") (pinfunction "3_3") (pintype "passive"))
      (node (ref "J11") (pin "4") (pinfunction "4_4") (pintype "passive"))
      (node (ref "J14") (pin "2") (pinfunction "2_2") (pintype "passive"))
      (node (ref "J19") (pin "6") (pinfunction "6_6") (pintype "passive"))
      (node (ref "J2") (pin "9") (pinfunction "9_9") (pintype "passive"))
      (node (ref "J20") (pin "2") (pinfunction "2_2") (pintype "passive"))
      (node (ref "J21") (pin "2") (pinfunction "2_2") (pintype "passive"))
      (node (ref "J22") (pin "2") (pinfunction "2_2") (pintype "passive"))
      (node (ref "J23") (pin "2") (pinfunction "2_2") (pintype "passive"))
      (node (ref "J24") (pin "2") (pinfunction "2_2") (pintype "passive"))
      (node (ref "J25") (pin "2") (pinfunction "2_2") (pintype "passive"))
      (node (ref "J27") (pin "10") (pinfunction "10_10") (pintype "passive"))
      (node (ref "J27") (pin "2") (pinfunction "2_2") (pintype "passive"))
      (node (ref "J33") (pin "1") (pinfunction "1_1") (pintype "passive"))
      (node (ref "J36") (pin "4") (pinfunction "4_4") (pintype "passive"))
      (node (ref "J39") (pin "1") (pinfunction "GND_1") (pintype "passive"))
      (node (ref "J42") (pin "2") (pinfunction "2_2") (pintype "passive"))
      (node (ref "J43") (pin "2") (pinfunction "2_2") (pintype "passive"))
      (node (ref "J44") (pin "2") (pinfunction "2_2") (pintype "passive"))
      (node (ref "J49") (pin "1") (pinfunction "1_1") (pintype "passive"))
      (node (ref "J50") (pin "1") (pinfunction "1_1") (pintype "passive"))
      (node (ref "J51") (pin "1") (pinfunction "1_1") (pintype "passive"))
      (node (ref "J52") (pin "1") (pinfunction "1_1") (pintype "passive"))
      (node (ref "J53") (pin "1") (pinfunction "1_1") (pintype "passive"))
      (node (ref "J6") (pin "9") (pinfunction "9_9") (pintype "passive"))
      (node (ref "K1") (pin "1") (pinfunction "1_1") (pintype "passive"))
      (node (ref "Q1") (pin "S") (pinfunction "2_S") (pintype "passive"))
      (node (ref "Q2") (pin "S") (pinfunction "2_S") (pintype "passive"))
      (node (ref "Q3") (pin "S") (pinfunction "2_S") (pintype "passive"))
      (node (ref "Q4") (pin "S") (pinfunction "2_S") (pintype "passive"))
      (node (ref "Q5") (pin "S") (pinfunction "2_S") (pintype "passive"))
      (node (ref "Q6") (pin "S") (pinfunction "2_S") (pintype "passive"))
      (node (ref "R12") (pin "1") (pinfunction "1_1") (pintype "passive"))
      (node (ref "R15") (pin "1") (pinfunction "1_1") (pintype "passive"))
      (node (ref "R17") (pin "1") (pinfunction "1_1") (pintype "passive"))
      (node (ref "R2") (pin "1") (pinfunction "1_1") (pintype "passive"))
      (node (ref "R26") (pin "1") (pinfunction "1_1") (pintype "passive"))
      (node (ref "R28") (pin "1") (pinfunction "1_1") (pintype "passive"))
      (node (ref "R31") (pin "1") (pinfunction "1_1") (pintype "passive"))
      (node (ref "R37") (pin "1") (pinfunction "1_1") (pintype "passive"))
      (node (ref "R39") (pin "1") (pinfunction "1_1") (pintype "passive"))
      (node (ref "R40") (pin "2") (pinfunction "2_2") (pintype "passive"))
      (node (ref "R43") (pin "1") (pinfunction "1_1") (pintype "passive"))
      (node (ref "R45") (pin "1") (pinfunction "1_1") (pintype "passive"))
      (node (ref "R5") (pin "2") (pinfunction "2_2") (pintype "passive"))
      (node (ref "R6") (pin "1") (pinfunction "1_1") (pintype "passive"))
      (node (ref "R9") (pin "1") (pinfunction "1_1") (pintype "passive"))
      (node (ref "U1") (pin "15") (pinfunction "GND_15") (pintype "passive"))
      (node (ref "U1") (pin "9") (pinfunction "GND_9") (pintype "passive"))
      (node (ref "U10") (pin "15") (pinfunction "GND_15") (pintype "passive"))
      (node (ref "U10") (pin "9") (pinfunction "GND_9") (pintype "passive"))
      (node (ref "U2") (pin "3") (pinfunction "GND_3") (pintype "passive"))
      (node (ref "U2") (pin "5") (pinfunction "ON/OFF_5") (pintype "passive"))
      (node (ref "U3") (pin "15") (pinfunction "GND_15") (pintype "passive"))
      (node (ref "U3") (pin "9") (pinfunction "GND_9") (pintype "passive"))
      (node (ref "U4") (pin "11") (pinfunction "GND_11") (pintype "passive"))
      (node (ref "U4") (pin "32") (pinfunction "GND_32") (pintype "passive"))
      (node (ref "U4") (pin "62") (pinfunction "GND_62") (pintype "passive"))
      (node (ref "U4") (pin "81") (pinfunction "GND_81") (pintype "passive"))
      (node (ref "U4") (pin "99") (pinfunction "GND_99") (pintype "passive"))
      (node (ref "U5") (pin "15") (pinfunction "GND_15") (pintype "passive"))
      (node (ref "U5") (pin "9") (pinfunction "GND_9") (pintype "passive"))
      (node (ref "U6") (pin "15") (pinfunction "GND_15") (pintype "passive"))
      (node (ref "U6") (pin "9") (pinfunction "GND_9") (pintype "passive"))
      (node (ref "U7") (pin "3") (pinfunction "GND_3") (pintype "passive"))
      (node (ref "U8") (pin "2") (pinfunction "GND_2") (pintype "passive"))
      (node (ref "U9") (pin "15") (pinfunction "GND_15") (pintype "passive"))
      (node (ref "U9") (pin "9") (pinfunction "GND_9") (pintype "passive"))
      (node (ref "Y1") (pin "2") (pinfunction "GND_2") (pintype "passive"))
      (node (ref "Z1") (pin "1") (pinfunction "1_1") (pintype "passive"))
      (node (ref "Z2") (pin "1") (pinfunction "1_1") (pintype "passive"))
      (node (ref "Z3") (pin "1") (pinfunction "1_1") (pintype "passive"))
    )
    (net (code "82") (name "Net-(C31-Pad1)") (class "Default")
      (node (ref "C31") (pin "1") (pinfunction "1_1") (pintype "passive"))
      (node (ref "LV1") (pin "1") (pinfunction "1_1") (pintype "passive"))
    )
    (net (code "83") (name "Net-(D1-K)") (class "Default")
      (node (ref "D1") (pin "2") (pinfunction "K_2") (pintype "passive"))
      (node (ref "L1") (pin "1") (pinfunction "1_1") (pintype "passive"))
      (node (ref "U2") (pin "2") (pinfunction "OUT_2") (pintype "passive"))
    )
    (net (code "84") (name "Net-(D2-A)") (class "Default")
      (node (ref "D2") (pin "1") (pinfunction "A_1") (pintype "passive"))
      (node (ref "R4") (pin "2") (pinfunction "2_2") (pintype "passive"))
    )
    (net (code "85") (name "Net-(D3-A)") (class "Default")
      (node (ref "D3") (pin "1") (pinfunction "A_1") (pintype "passive"))
      (node (ref "R11") (pin "2") (pinfunction "2_2") (pintype "passive"))
    )
    (net (code "86") (name "Net-(D4-A)") (class "Default")
      (node (ref "D4") (pin "1") (pinfunction "A_1") (pintype "passive"))
      (node (ref "R14") (pin "2") (pinfunction "2_2") (pintype "passive"))
    )
    (net (code "87") (name "Net-(D5-A)") (class "Default")
      (node (ref "D5") (pin "1") (pinfunction "A_1") (pintype "passive"))
      (node (ref "R18") (pin "1") (pinfunction "1_1") (pintype "passive"))
    )
    (net (code "88") (name "Net-(D7-A)") (class "Default")
      (node (ref "D7") (pin "1") (pinfunction "A_1") (pintype "passive"))
      (node (ref "R24") (pin "1") (pinfunction "1_1") (pintype "passive"))
    )
    (net (code "89") (name "Net-(D8-A)") (class "Default")
      (node (ref "D8") (pin "1") (pinfunction "A_1") (pintype "passive"))
      (node (ref "R25") (pin "2") (pinfunction "2_2") (pintype "passive"))
    )
    (net (code "90") (name "Net-(D9-K)") (class "Default")
      (node (ref "C21") (pin "1") (pinfunction "1_1") (pintype "passive"))
      (node (ref "D9") (pin "2") (pinfunction "K_2") (pintype "passive"))
      (node (ref "U8") (pin "1") (pinfunction "BOOST_1") (pintype "passive"))
    )
    (net (code "91") (name "Net-(D12-K)") (class "Default")
      (node (ref "C21") (pin "2") (pinfunction "2_2") (pintype "passive"))
      (node (ref "D12") (pin "2") (pinfunction "K_2") (pintype "passive"))
      (node (ref "L2") (pin "1") (pinfunction "1_1") (pintype "passive"))
      (node (ref "U8") (pin "6") (pinfunction "SW_6") (pintype "passive"))
    )
    (net (code "92") (name "Net-(D13-A)") (class "Default")
      (node (ref "D13") (pin "1") (pinfunction "A_1") (pintype "passive"))
      (node (ref "R36") (pin "2") (pinfunction "2_2") (pintype "passive"))
    )
    (net (code "93") (name "Net-(D15-A)") (class "Default")
      (node (ref "D15") (pin "1") (pinfunction "A_1") (pintype "passive"))
      (node (ref "R42") (pin "2") (pinfunction "2_2") (pintype "passive"))
    )
    (net (code "94") (name "Net-(F1-Pad2)") (class "Default")
      (node (ref "F1") (pin "2") (pinfunction "2_2") (pintype "passive"))
      (node (ref "F2") (pin "2") (pinfunction "2_2") (pintype "passive"))
      (node (ref "J33") (pin "2") (pinfunction "2_2") (pintype "passive"))
    )
    (net (code "95") (name "Net-(J17-Pad2)") (class "Default")
      (node (ref "J17") (pin "2") (pinfunction "2_2") (pintype "passive"))
      (node (ref "J18") (pin "1") (pinfunction "1_1") (pintype "passive"))
    )
    (net (code "96") (name "Net-(J30-Pad2)") (class "Default")
      (node (ref "J30") (pin "2") (pinfunction "2_2") (pintype "passive"))
      (node (ref "J31") (pin "1") (pinfunction "1_1") (pintype "passive"))
      (node (ref "J32") (pin "1") (pinfunction "1_1") (pintype "passive"))
    )
    (net (code "97") (name "Net-(J38-Pad2)") (class "Default")
      (node (ref "J38") (pin "2") (pinfunction "2_2") (pintype "passive"))
      (node (ref "J40") (pin "1") (pinfunction "1_1") (pintype "passive"))
      (node (ref "J41") (pin "1") (pinfunction "1_1") (pintype "passive"))
    )
    (net (code "98") (name "Net-(J39-Pad5)") (class "Default")
      (node (ref "J39") (pin "5") (pinfunction "5_5") (pintype "passive"))
      (node (ref "LV1") (pin "2") (pinfunction "2_2") (pintype "passive"))
    )
    (net (code "99") (name "Net-(Q1-1)") (class "Default")
      (node (ref "Q1") (pin "G") (pinfunction "1_G") (pintype "passive"))
      (node (ref "R3") (pin "1") (pinfunction "1_1") (pintype "passive"))
    )
    (net (code "100") (name "Net-(Q1-3)") (class "Default")
      (node (ref "J1") (pin "2") (pinfunction "2_2") (pintype "passive"))
      (node (ref "Q1") (pin "D") (pinfunction "3_D") (pintype "passive"))
    )
    (net (code "101") (name "Net-(Q2-1)") (class "Default")
      (node (ref "Q2") (pin "G") (pinfunction "1_G") (pintype "passive"))
      (node (ref "R10") (pin "1") (pinfunction "1_1") (pintype "passive"))
    )
    (net (code "102") (name "Net-(Q2-3)") (class "Default")
      (node (ref "J7") (pin "2") (pinfunction "2_2") (pintype "passive"))
      (node (ref "Q2") (pin "D") (pinfunction "3_D") (pintype "passive"))
    )
    (net (code "103") (name "Net-(Q3-1)") (class "Default")
      (node (ref "Q3") (pin "G") (pinfunction "1_G") (pintype "passive"))
      (node (ref "R13") (pin "1") (pinfunction "1_1") (pintype "passive"))
    )
    (net (code "104") (name "Net-(Q3-3)") (class "Default")
      (node (ref "J12") (pin "1") (pinfunction "1_1") (pintype "passive"))
      (node (ref "Q3") (pin "D") (pinfunction "3_D") (pintype "passive"))
    )
    (net (code "105") (name "Net-(Q4-1)") (class "Default")
      (node (ref "Q4") (pin "G") (pinfunction "1_G") (pintype "passive"))
      (node (ref "R22") (pin "1") (pinfunction "1_1") (pintype "passive"))
    )
    (net (code "106") (name "Net-(Q4-3)") (class "Default")
      (node (ref "J18") (pin "2") (pinfunction "2_2") (pintype "passive"))
      (node (ref "Q4") (pin "D") (pinfunction "3_D") (pintype "passive"))
    )
    (net (code "107") (name "Net-(Q5-1)") (class "Default")
      (node (ref "Q5") (pin "G") (pinfunction "1_G") (pintype "passive"))
      (node (ref "R33") (pin "1") (pinfunction "1_1") (pintype "passive"))
    )
    (net (code "108") (name "Net-(Q5-3)") (class "Default")
      (node (ref "J31") (pin "2") (pinfunction "2_2") (pintype "passive"))
      (node (ref "J32") (pin "2") (pinfunction "2_2") (pintype "passive"))
      (node (ref "Q5") (pin "D") (pinfunction "3_D") (pintype "passive"))
    )
    (net (code "109") (name "Net-(Q6-1)") (class "Default")
      (node (ref "Q6") (pin "G") (pinfunction "1_G") (pintype "passive"))
      (node (ref "R41") (pin "1") (pinfunction "1_1") (pintype "passive"))
    )
    (net (code "110") (name "Net-(Q6-3)") (class "Default")
      (node (ref "J40") (pin "2") (pinfunction "2_2") (pintype "passive"))
      (node (ref "J41") (pin "2") (pinfunction "2_2") (pintype "passive"))
      (node (ref "Q6") (pin "D") (pinfunction "3_D") (pintype "passive"))
    )
    (net (code "111") (name "Net-(U1-1A)") (class "Default")
      (node (ref "J3") (pin "3") (pinfunction "3_3") (pintype "passive"))
      (node (ref "J5") (pin "3") (pinfunction "3_3") (pintype "passive"))
      (node (ref "U1") (pin "12") (pinfunction "1A_12") (pintype "passive"))
    )
    (net (code "112") (name "Net-(U1-1B)") (class "Default")
      (node (ref "J3") (pin "4") (pinfunction "4_4") (pintype "passive"))
      (node (ref "J5") (pin "4") (pinfunction "4_4") (pintype "passive"))
      (node (ref "U1") (pin "11") (pinfunction "1B_11") (pintype "passive"))
    )
    (net (code "113") (name "Net-(U1-2A)") (class "Default")
      (node (ref "J3") (pin "2") (pinfunction "2_2") (pintype "passive"))
      (node (ref "J5") (pin "2") (pinfunction "2_2") (pintype "passive"))
      (node (ref "U1") (pin "13") (pinfunction "2A_13") (pintype "passive"))
    )
    (net (code "114") (name "Net-(U1-2B)") (class "Default")
      (node (ref "J3") (pin "1") (pinfunction "1_1") (pintype "passive"))
      (node (ref "J5") (pin "1") (pinfunction "1_1") (pintype "passive"))
      (node (ref "U1") (pin "14") (pinfunction "2B_14") (pintype "passive"))
    )
    (net (code "115") (name "Net-(U1-MS1)") (class "Default")
      (node (ref "J4") (pin "1") (pinfunction "1_1") (pintype "passive"))
      (node (ref "R2") (pin "2") (pinfunction "2_2") (pintype "passive"))
      (node (ref "U1") (pin "2") (pinfunction "MS1_2") (pintype "passive"))
    )
    (net (code "116") (name "Net-(U1-MS2)") (class "Default")
      (node (ref "J4") (pin "2") (pinfunction "2_2") (pintype "passive"))
      (node (ref "U1") (pin "3") (pinfunction "MS2_3") (pintype "passive"))
    )
    (net (code "117") (name "Net-(U1-MS3)") (class "Default")
      (node (ref "J4") (pin "3") (pinfunction "3_3") (pintype "passive"))
      (node (ref "U1") (pin "4") (pinfunction "MS3_4") (pintype "passive"))
    )
    (net (code "118") (name "Net-(U1-RST)") (class "Default")
      (node (ref "U1") (pin "5") (pinfunction "RST_5") (pintype "passive"))
      (node (ref "U1") (pin "6") (pinfunction "SLEEP_6") (pintype "passive"))
    )
    (net (code "119") (name "Net-(U2-FB)") (class "Default")
      (node (ref "C7") (pin "1") (pinfunction "1_1") (pintype "passive"))
      (node (ref "R5") (pin "1") (pinfunction "1_1") (pintype "passive"))
      (node (ref "R7") (pin "1") (pinfunction "1_1") (pintype "passive"))
      (node (ref "U2") (pin "4") (pinfunction "FB_4") (pintype "passive"))
    )
    (net (code "120") (name "Net-(U3-1A)") (class "Default")
      (node (ref "J10") (pin "3") (pinfunction "3_3") (pintype "passive"))
      (node (ref "J8") (pin "3") (pinfunction "3_3") (pintype "passive"))
      (node (ref "U3") (pin "12") (pinfunction "1A_12") (pintype "passive"))
    )
    (net (code "121") (name "Net-(U3-1B)") (class "Default")
      (node (ref "J10") (pin "4") (pinfunction "4_4") (pintype "passive"))
      (node (ref "J8") (pin "4") (pinfunction "4_4") (pintype "passive"))
      (node (ref "U3") (pin "11") (pinfunction "1B_11") (pintype "passive"))
    )
    (net (code "122") (name "Net-(U3-2A)") (class "Default")
      (node (ref "J10") (pin "2") (pinfunction "2_2") (pintype "passive"))
      (node (ref "J8") (pin "2") (pinfunction "2_2") (pintype "passive"))
      (node (ref "U3") (pin "13") (pinfunction "2A_13") (pintype "passive"))
    )
    (net (code "123") (name "Net-(U3-2B)") (class "Default")
      (node (ref "J10") (pin "1") (pinfunction "1_1") (pintype "passive"))
      (node (ref "J8") (pin "1") (pinfunction "1_1") (pintype "passive"))
      (node (ref "U3") (pin "14") (pinfunction "2B_14") (pintype "passive"))
    )
    (net (code "124") (name "Net-(U3-MS1)") (class "Default")
      (node (ref "J9") (pin "1") (pinfunction "1_1") (pintype "passive"))
      (node (ref "R9") (pin "2") (pinfunction "2_2") (pintype "passive"))
      (node (ref "U3") (pin "2") (pinfunction "MS1_2") (pintype "passive"))
    )
    (net (code "125") (name "Net-(U3-MS2)") (class "Default")
      (node (ref "J9") (pin "2") (pinfunction "2_2") (pintype "passive"))
      (node (ref "U3") (pin "3") (pinfunction "MS2_3") (pintype "passive"))
    )
    (net (code "126") (name "Net-(U3-MS3)") (class "Default")
      (node (ref "J9") (pin "3") (pinfunction "3_3") (pintype "passive"))
      (node (ref "U3") (pin "4") (pinfunction "MS3_4") (pintype "passive"))
    )
    (net (code "127") (name "Net-(U3-RST)") (class "Default")
      (node (ref "U3") (pin "5") (pinfunction "RST_5") (pintype "passive"))
      (node (ref "U3") (pin "6") (pinfunction "SLEEP_6") (pintype "passive"))
    )
    (net (code "128") (name "Net-(U4-XTAL1)") (class "Default")
      (node (ref "C16") (pin "1") (pinfunction "1_1") (pintype "passive"))
      (node (ref "R23") (pin "1") (pinfunction "1_1") (pintype "passive"))
      (node (ref "U4") (pin "34") (pinfunction "XTAL1_34") (pintype "passive"))
      (node (ref "Y1") (pin "3") (pinfunction "OUT_3") (pintype "passive"))
    )
    (net (code "129") (name "Net-(U4-XTAL2)") (class "Default")
      (node (ref "C18") (pin "2") (pinfunction "2_2") (pintype "passive"))
      (node (ref "R23") (pin "2") (pinfunction "2_2") (pintype "passive"))
      (node (ref "U4") (pin "33") (pinfunction "XTAL2_33") (pintype "passive"))
      (node (ref "Y1") (pin "1") (pinfunction "IN_1") (pintype "passive"))
    )
    (net (code "130") (name "Net-(U5-1A)") (class "Default")
      (node (ref "J13") (pin "3") (pinfunction "3_3") (pintype "passive"))
      (node (ref "J16") (pin "3") (pinfunction "3_3") (pintype "passive"))
      (node (ref "U5") (pin "12") (pinfunction "1A_12") (pintype "passive"))
    )
    (net (code "131") (name "Net-(U5-1B)") (class "Default")
      (node (ref "J13") (pin "4") (pinfunction "4_4") (pintype "passive"))
      (node (ref "J16") (pin "4") (pinfunction "4_4") (pintype "passive"))
      (node (ref "U5") (pin "11") (pinfunction "1B_11") (pintype "passive"))
    )
    (net (code "132") (name "Net-(U5-2A)") (class "Default")
      (node (ref "J13") (pin "2") (pinfunction "2_2") (pintype "passive"))
      (node (ref "J16") (pin "2") (pinfunction "2_2") (pintype "passive"))
      (node (ref "U5") (pin "13") (pinfunction "2A_13") (pintype "passive"))
    )
    (net (code "133") (name "Net-(U5-2B)") (class "Default")
      (node (ref "J13") (pin "1") (pinfunction "1_1") (pintype "passive"))
      (node (ref "J16") (pin "1") (pinfunction "1_1") (pintype "passive"))
      (node (ref "U5") (pin "14") (pinfunction "2B_14") (pintype "passive"))
    )
    (net (code "134") (name "Net-(U5-MS1)") (class "Default")
      (node (ref "J15") (pin "1") (pinfunction "1_1") (pintype "passive"))
      (node (ref "R17") (pin "2") (pinfunction "2_2") (pintype "passive"))
      (node (ref "U5") (pin "2") (pinfunction "MS1_2") (pintype "passive"))
    )
    (net (code "135") (name "Net-(U5-MS2)") (class "Default")
      (node (ref "J15") (pin "2") (pinfunction "2_2") (pintype "passive"))
      (node (ref "U5") (pin "3") (pinfunction "MS2_3") (pintype "passive"))
    )
    (net (code "136") (name "Net-(U5-MS3)") (class "Default")
      (node (ref "J15") (pin "3") (pinfunction "3_3") (pintype "passive"))
      (node (ref "U5") (pin "4") (pinfunction "MS3_4") (pintype "passive"))
    )
    (net (code "137") (name "Net-(U5-RST)") (class "Default")
      (node (ref "U5") (pin "5") (pinfunction "RST_5") (pintype "passive"))
      (node (ref "U5") (pin "6") (pinfunction "SLEEP_6") (pintype "passive"))
    )
    (net (code "138") (name "Net-(U6-1A)") (class "Default")
      (node (ref "J26") (pin "3") (pinfunction "3_3") (pintype "passive"))
      (node (ref "J29") (pin "3") (pinfunction "3_3") (pintype "passive"))
      (node (ref "U6") (pin "12") (pinfunction "1A_12") (pintype "passive"))
    )
    (net (code "139") (name "Net-(U6-1B)") (class "Default")
      (node (ref "J26") (pin "4") (pinfunction "4_4") (pintype "passive"))
      (node (ref "J29") (pin "4") (pinfunction "4_4") (pintype "passive"))
      (node (ref "U6") (pin "11") (pinfunction "1B_11") (pintype "passive"))
    )
    (net (code "140") (name "Net-(U6-2A)") (class "Default")
      (node (ref "J26") (pin "2") (pinfunction "2_2") (pintype "passive"))
      (node (ref "J29") (pin "2") (pinfunction "2_2") (pintype "passive"))
      (node (ref "U6") (pin "13") (pinfunction "2A_13") (pintype "passive"))
    )
    (net (code "141") (name "Net-(U6-2B)") (class "Default")
      (node (ref "J26") (pin "1") (pinfunction "1_1") (pintype "passive"))
      (node (ref "J29") (pin "1") (pinfunction "1_1") (pintype "passive"))
      (node (ref "U6") (pin "14") (pinfunction "2B_14") (pintype "passive"))
    )
    (net (code "142") (name "Net-(U6-MS1)") (class "Default")
      (node (ref "J28") (pin "1") (pinfunction "1_1") (pintype "passive"))
      (node (ref "R28") (pin "2") (pinfunction "2_2") (pintype "passive"))
      (node (ref "U6") (pin "2") (pinfunction "MS1_2") (pintype "passive"))
    )
    (net (code "143") (name "Net-(U6-MS2)") (class "Default")
      (node (ref "J28") (pin "2") (pinfunction "2_2") (pintype "passive"))
      (node (ref "U6") (pin "3") (pinfunction "MS2_3") (pintype "passive"))
    )
    (net (code "144") (name "Net-(U6-MS3)") (class "Default")
      (node (ref "J28") (pin "3") (pinfunction "3_3") (pintype "passive"))
      (node (ref "U6") (pin "4") (pinfunction "MS3_4") (pintype "passive"))
    )
    (net (code "145") (name "Net-(U6-RST)") (class "Default")
      (node (ref "U6") (pin "5") (pinfunction "RST_5") (pintype "passive"))
      (node (ref "U6") (pin "6") (pinfunction "SLEEP_6") (pintype "passive"))
    )
    (net (code "146") (name "Net-(U7-D+)") (class "Default")
      (node (ref "R32") (pin "1") (pinfunction "1_1") (pintype "passive"))
      (node (ref "U7") (pin "4") (pinfunction "D+_4") (pintype "passive"))
    )
    (net (code "147") (name "Net-(U7-D-)") (class "Default")
      (node (ref "R34") (pin "1") (pinfunction "1_1") (pintype "passive"))
      (node (ref "U7") (pin "5") (pinfunction "D-_5") (pintype "passive"))
    )
    (net (code "148") (name "Net-(U7-DTR)") (class "Default")
      (node (ref "C20") (pin "2") (pinfunction "2_2") (pintype "passive"))
      (node (ref "R31") (pin "2") (pinfunction "2_2") (pintype "passive"))
      (node (ref "U7") (pin "28") (pinfunction "DTR_28") (pintype "passive"))
    )
    (net (code "149") (name "Net-(U7-RXD)") (class "Default")
      (node (ref "R29") (pin "2") (pinfunction "2_2") (pintype "passive"))
      (node (ref "U7") (pin "25") (pinfunction "RXD_25") (pintype "passive"))
    )
    (net (code "150") (name "Net-(U7-TXD)") (class "Default")
      (node (ref "R30") (pin "2") (pinfunction "2_2") (pintype "passive"))
      (node (ref "U7") (pin "26") (pinfunction "TXD_26") (pintype "passive"))
    )
    (net (code "151") (name "Net-(U7-VDD)") (class "Default")
      (node (ref "C26") (pin "1") (pinfunction "1_1") (pintype "passive"))
      (node (ref "U7") (pin "6") (pinfunction "VDD_6") (pintype "passive"))
    )
    (net (code "152") (name "Net-(U8-FB)") (class "Default")
      (node (ref "R35") (pin "2") (pinfunction "2_2") (pintype "passive"))
      (node (ref "R40") (pin "1") (pinfunction "1_1") (pintype "passive"))
      (node (ref "U8") (pin "3") (pinfunction "FB_3") (pintype "passive"))
    )
    (net (code "153") (name "Net-(U9-1A)") (class "Default")
      (node (ref "J34") (pin "3") (pinfunction "3_3") (pintype "passive"))
      (node (ref "J37") (pin "3") (pinfunction "3_3") (pintype "passive"))
      (node (ref "U9") (pin "12") (pinfunction "1A_12") (pintype "passive"))
    )
    (net (code "154") (name "Net-(U9-1B)") (class "Default")
      (node (ref "J34") (pin "4") (pinfunction "4_4") (pintype "passive"))
      (node (ref "J37") (pin "4") (pinfunction "4_4") (pintype "passive"))
      (node (ref "U9") (pin "11") (pinfunction "1B_11") (pintype "passive"))
    )
    (net (code "155") (name "Net-(U9-2A)") (class "Default")
      (node (ref "J34") (pin "2") (pinfunction "2_2") (pintype "passive"))
      (node (ref "J37") (pin "2") (pinfunction "2_2") (pintype "passive"))
      (node (ref "U9") (pin "13") (pinfunction "2A_13") (pintype "passive"))
    )
    (net (code "156") (name "Net-(U9-2B)") (class "Default")
      (node (ref "J34") (pin "1") (pinfunction "1_1") (pintype "passive"))
      (node (ref "J37") (pin "1") (pinfunction "1_1") (pintype "passive"))
      (node (ref "U9") (pin "14") (pinfunction "2B_14") (pintype "passive"))
    )
    (net (code "157") (name "Net-(U9-MS1)") (class "Default")
      (node (ref "J35") (pin "1") (pinfunction "1_1") (pintype "passive"))
      (node (ref "R39") (pin "2") (pinfunction "2_2") (pintype "passive"))
      (node (ref "U9") (pin "2") (pinfunction "MS1_2") (pintype "passive"))
    )
    (net (code "158") (name "Net-(U9-MS2)") (class "Default")
      (node (ref "J35") (pin "2") (pinfunction "2_2") (pintype "passive"))
      (node (ref "U9") (pin "3") (pinfunction "MS2_3") (pintype "passive"))
    )
    (net (code "159") (name "Net-(U9-MS3)") (class "Default")
      (node (ref "J35") (pin "3") (pinfunction "3_3") (pintype "passive"))
      (node (ref "U9") (pin "4") (pinfunction "MS3_4") (pintype "passive"))
    )
    (net (code "160") (name "Net-(U9-RST)") (class "Default")
      (node (ref "U9") (pin "5") (pinfunction "RST_5") (pintype "passive"))
      (node (ref "U9") (pin "6") (pinfunction "SLEEP_6") (pintype "passive"))
    )
    (net (code "161") (name "Net-(U10-1A)") (class "Default")
      (node (ref "J46") (pin "3") (pinfunction "3_3") (pintype "passive"))
      (node (ref "J48") (pin "3") (pinfunction "3_3") (pintype "passive"))
      (node (ref "U10") (pin "12") (pinfunction "1A_12") (pintype "passive"))
    )
    (net (code "162") (name "Net-(U10-1B)") (class "Default")
      (node (ref "J46") (pin "4") (pinfunction "4_4") (pintype "passive"))
      (node (ref "J48") (pin "4") (pinfunction "4_4") (pintype "passive"))
      (node (ref "U10") (pin "11") (pinfunction "1B_11") (pintype "passive"))
    )
    (net (code "163") (name "Net-(U10-2A)") (class "Default")
      (node (ref "J46") (pin "2") (pinfunction "2_2") (pintype "passive"))
      (node (ref "J48") (pin "2") (pinfunction "2_2") (pintype "passive"))
      (node (ref "U10") (pin "13") (pinfunction "2A_13") (pintype "passive"))
    )
    (net (code "164") (name "Net-(U10-2B)") (class "Default")
      (node (ref "J46") (pin "1") (pinfunction "1_1") (pintype "passive"))
      (node (ref "J48") (pin "1") (pinfunction "1_1") (pintype "passive"))
      (node (ref "U10") (pin "14") (pinfunction "2B_14") (pintype "passive"))
    )
    (net (code "165") (name "Net-(U10-MS1)") (class "Default")
      (node (ref "J47") (pin "1") (pinfunction "1_1") (pintype "passive"))
      (node (ref "R45") (pin "2") (pinfunction "2_2") (pintype "passive"))
      (node (ref "U10") (pin "2") (pinfunction "MS1_2") (pintype "passive"))
    )
    (net (code "166") (name "Net-(U10-MS2)") (class "Default")
      (node (ref "J47") (pin "2") (pinfunction "2_2") (pintype "passive"))
      (node (ref "U10") (pin "3") (pinfunction "MS2_3") (pintype "passive"))
    )
    (net (code "167") (name "Net-(U10-MS3)") (class "Default")
      (node (ref "J47") (pin "3") (pinfunction "3_3") (pintype "passive"))
      (node (ref "U10") (pin "4") (pinfunction "MS3_4") (pintype "passive"))
    )
    (net (code "168") (name "Net-(U10-RST)") (class "Default")
      (node (ref "U10") (pin "5") (pinfunction "RST_5") (pintype "passive"))
      (node (ref "U10") (pin "6") (pinfunction "SLEEP_6") (pintype "passive"))
    )
    (net (code "169") (name "USB-VCC") (class "Default")
      (node (ref "C31") (pin "2") (pinfunction "2_2") (pintype "passive"))
      (node (ref "J36") (pin "1") (pinfunction "1_1") (pintype "passive"))
      (node (ref "J39") (pin "4") (pinfunction "+5V_4") (pintype "passive"))
      (node (ref "J45") (pin "3") (pinfunction "3_3") (pintype "passive"))
      (node (ref "Z1") (pin "2") (pinfunction "2_2") (pintype "passive"))
    )
    (net (code "170") (name "VIN1") (class "Default")
      (node (ref "C1") (pin "1") (pinfunction "+_1") (pintype "passive"))
      (node (ref "C13") (pin "1") (pinfunction "+_1") (pintype "passive"))
      (node (ref "C19") (pin "1") (pinfunction "+_1") (pintype "passive"))
      (node (ref "C27") (pin "1") (pinfunction "+_1") (pintype "passive"))
      (node (ref "C32") (pin "1") (pinfunction "+_1") (pintype "passive"))
      (node (ref "C6") (pin "1") (pinfunction "+_1") (pintype "passive"))
      (node (ref "C9") (pin "1") (pinfunction "+_1") (pintype "passive"))
      (node (ref "D10") (pin "1") (pinfunction "A_1") (pintype "passive"))
      (node (ref "D11") (pin "2") (pinfunction "K_2") (pintype "passive"))
      (node (ref "F1") (pin "1") (pinfunction "1_1") (pintype "passive"))
      (node (ref "J1") (pin "1") (pinfunction "1_1") (pintype "passive"))
      (node (ref "J17") (pin "1") (pinfunction "1_1") (pintype "passive"))
      (node (ref "J30") (pin "1") (pinfunction "1_1") (pintype "passive"))
      (node (ref "J38") (pin "1") (pinfunction "1_1") (pintype "passive"))
      (node (ref "J42") (pin "1") (pinfunction "1_1") (pintype "passive"))
      (node (ref "J43") (pin "1") (pinfunction "1_1") (pintype "passive"))
      (node (ref "J7") (pin "1") (pinfunction "1_1") (pintype "passive"))
      (node (ref "U1") (pin "16") (pinfunction "VMOT_16") (pintype "passive"))
      (node (ref "U10") (pin "16") (pinfunction "VMOT_16") (pintype "passive"))
      (node (ref "U2") (pin "1") (pinfunction "VIN_1") (pintype "passive"))
      (node (ref "U3") (pin "16") (pinfunction "VMOT_16") (pintype "passive"))
      (node (ref "U5") (pin "16") (pinfunction "VMOT_16") (pintype "passive"))
      (node (ref "U6") (pin "16") (pinfunction "VMOT_16") (pintype "passive"))
      (node (ref "U9") (pin "16") (pinfunction "VMOT_16") (pintype "passive"))
    )
    (net (code "171") (name "VIN2") (class "Default")
      (node (ref "D14") (pin "2") (pinfunction "K_2") (pintype "passive"))
      (node (ref "F2") (pin "1") (pinfunction "1_1") (pintype "passive"))
      (node (ref "J12") (pin "2") (pinfunction "2_2") (pintype "passive"))
    )
    (net (code "172") (name "unconnected-(J27-Pad8)") (class "Default")
      (node (ref "J27") (pin "8") (pinfunction "8_8") (pintype "passive"))
    )
    (net (code "173") (name "unconnected-(U4-(CLKO{slash}ICP3{slash}INT7)_PE7-Pad9)") (class "Default")
      (node (ref "U4") (pin "9") (pinfunction "(CLKO/ICP3/INT7)_PE7_9") (pintype "passive"))
    )
    (net (code "174") (name "unconnected-(U4-(ICP1)_PD4-Pad47)") (class "Default")
      (node (ref "U4") (pin "47") (pinfunction "(ICP1)_PD4_47") (pintype "passive"))
    )
    (net (code "175") (name "unconnected-(U4-(OC2A{slash}PCINT4)_PB4-Pad23)") (class "Default")
      (node (ref "U4") (pin "23") (pinfunction "(OC2A/PCINT4)_PB4_23") (pintype "passive"))
    )
    (net (code "176") (name "unconnected-(U4-(T1)_PD6-Pad49)") (class "Default")
      (node (ref "U4") (pin "49") (pinfunction "(T1)_PD6_49") (pintype "passive"))
    )
    (net (code "177") (name "unconnected-(U4-(T3{slash}INT6)_PE6-Pad8)") (class "Default")
      (node (ref "U4") (pin "8") (pinfunction "(T3/INT6)_PE6_8") (pintype "passive"))
    )
    (net (code "178") (name "unconnected-(U4-(T4)_PH7-Pad27)") (class "Default")
      (node (ref "U4") (pin "27") (pinfunction "(T4)_PH7_27") (pintype "passive"))
    )
    (net (code "179") (name "unconnected-(U4-(TOSC1)_PG4-Pad29)") (class "Default")
      (node (ref "U4") (pin "29") (pinfunction "(TOSC1)_PG4_29") (pintype "passive"))
    )
    (net (code "180") (name "unconnected-(U4-(TOSC2)_PG3-Pad28)") (class "Default")
      (node (ref "U4") (pin "28") (pinfunction "(TOSC2)_PG3_28") (pintype "passive"))
    )
    (net (code "181") (name "unconnected-(U4-(XCK1)_PD5-Pad48)") (class "Default")
      (node (ref "U4") (pin "48") (pinfunction "(XCK1)_PD5_48") (pintype "passive"))
    )
    (net (code "182") (name "unconnected-(U4-(XCK2)_PH2-Pad14)") (class "Default")
      (node (ref "U4") (pin "14") (pinfunction "(XCK2)_PH2_14") (pintype "passive"))
    )
    (net (code "183") (name "unconnected-(U4-PJ2_(XCK3{slash}PCINT11)-Pad65)") (class "Default")
      (node (ref "U4") (pin "65") (pinfunction "PJ2_(XCK3/PCINT11)_65") (pintype "passive"))
    )
    (net (code "184") (name "unconnected-(U4-PJ3_(PCINT12)-Pad66)") (class "Default")
      (node (ref "U4") (pin "66") (pinfunction "PJ3_(PCINT12)_66") (pintype "passive"))
    )
    (net (code "185") (name "unconnected-(U4-PJ4_(PCINT13)-Pad67)") (class "Default")
      (node (ref "U4") (pin "67") (pinfunction "PJ4_(PCINT13)_67") (pintype "passive"))
    )
    (net (code "186") (name "unconnected-(U4-PJ5_(PCINT14)-Pad68)") (class "Default")
      (node (ref "U4") (pin "68") (pinfunction "PJ5_(PCINT14)_68") (pintype "passive"))
    )
    (net (code "187") (name "unconnected-(U4-PJ6_(PCINT15)-Pad69)") (class "Default")
      (node (ref "U4") (pin "69") (pinfunction "PJ6_(PCINT15)_69") (pintype "passive"))
    )
    (net (code "188") (name "unconnected-(U4-PJ7-Pad79)") (class "Default")
      (node (ref "U4") (pin "79") (pinfunction "PJ7_79") (pintype "passive"))
    )
    (net (code "189") (name "unconnected-(U7-CTS-Pad23)") (class "Default")
      (node (ref "U7") (pin "23") (pinfunction "CTS_23") (pintype "passive"))
    )
    (net (code "190") (name "unconnected-(U7-DCD-Pad1)") (class "Default")
      (node (ref "U7") (pin "1") (pinfunction "DCD_1") (pintype "passive"))
    )
    (net (code "191") (name "unconnected-(U7-DSR-Pad27)") (class "Default")
      (node (ref "U7") (pin "27") (pinfunction "DSR_27") (pintype "passive"))
    )
    (net (code "192") (name "unconnected-(U7-NC-Pad10)") (class "Default")
      (node (ref "U7") (pin "10") (pinfunction "NC_10") (pintype "passive"))
    )
    (net (code "193") (name "unconnected-(U7-NC-Pad13)") (class "Default")
      (node (ref "U7") (pin "13") (pinfunction "NC_13") (pintype "passive"))
    )
    (net (code "194") (name "unconnected-(U7-NC-Pad14)") (class "Default")
      (node (ref "U7") (pin "14") (pinfunction "NC_14") (pintype "passive"))
    )
    (net (code "195") (name "unconnected-(U7-NC-Pad15)") (class "Default")
      (node (ref "U7") (pin "15") (pinfunction "NC_15") (pintype "passive"))
    )
    (net (code "196") (name "unconnected-(U7-NC-Pad16)") (class "Default")
      (node (ref "U7") (pin "16") (pinfunction "NC_16") (pintype "passive"))
    )
    (net (code "197") (name "unconnected-(U7-NC-Pad17)") (class "Default")
      (node (ref "U7") (pin "17") (pinfunction "NC_17") (pintype "passive"))
    )
    (net (code "198") (name "unconnected-(U7-NC-Pad18)") (class "Default")
      (node (ref "U7") (pin "18") (pinfunction "NC_18") (pintype "passive"))
    )
    (net (code "199") (name "unconnected-(U7-NC-Pad19)") (class "Default")
      (node (ref "U7") (pin "19") (pinfunction "NC_19") (pintype "passive"))
    )
    (net (code "200") (name "unconnected-(U7-NC-Pad20)") (class "Default")
      (node (ref "U7") (pin "20") (pinfunction "NC_20") (pintype "passive"))
    )
    (net (code "201") (name "unconnected-(U7-NC-Pad21)") (class "Default")
      (node (ref "U7") (pin "21") (pinfunction "NC_21") (pintype "passive"))
    )
    (net (code "202") (name "unconnected-(U7-NC-Pad22)") (class "Default")
      (node (ref "U7") (pin "22") (pinfunction "NC_22") (pintype "passive"))
    )
    (net (code "203") (name "unconnected-(U7-RI-Pad2)") (class "Default")
      (node (ref "U7") (pin "2") (pinfunction "RI_2") (pintype "passive"))
    )
    (net (code "204") (name "unconnected-(U7-RST-Pad9)") (class "Default")
      (node (ref "U7") (pin "9") (pinfunction "RST_9") (pintype "passive"))
    )
    (net (code "205") (name "unconnected-(U7-RTS-Pad24)") (class "Default")
      (node (ref "U7") (pin "24") (pinfunction "RTS_24") (pintype "passive"))
    )
    (net (code "206") (name "unconnected-(U7-SUSPEND-Pad11)") (class "Default")
      (node (ref "U7") (pin "11") (pinfunction "SUSPEND_11") (pintype "passive"))
    )
    (net (code "207") (name "unconnected-(U7-SUSPEND-Pad12)") (class "Default")
      (node (ref "U7") (pin "12") (pinfunction "SUSPEND_12") (pintype "passive"))
    )
  )
)
